# moire_v2_5.net
KiCad netlist of a schematic drawn in EAGLE
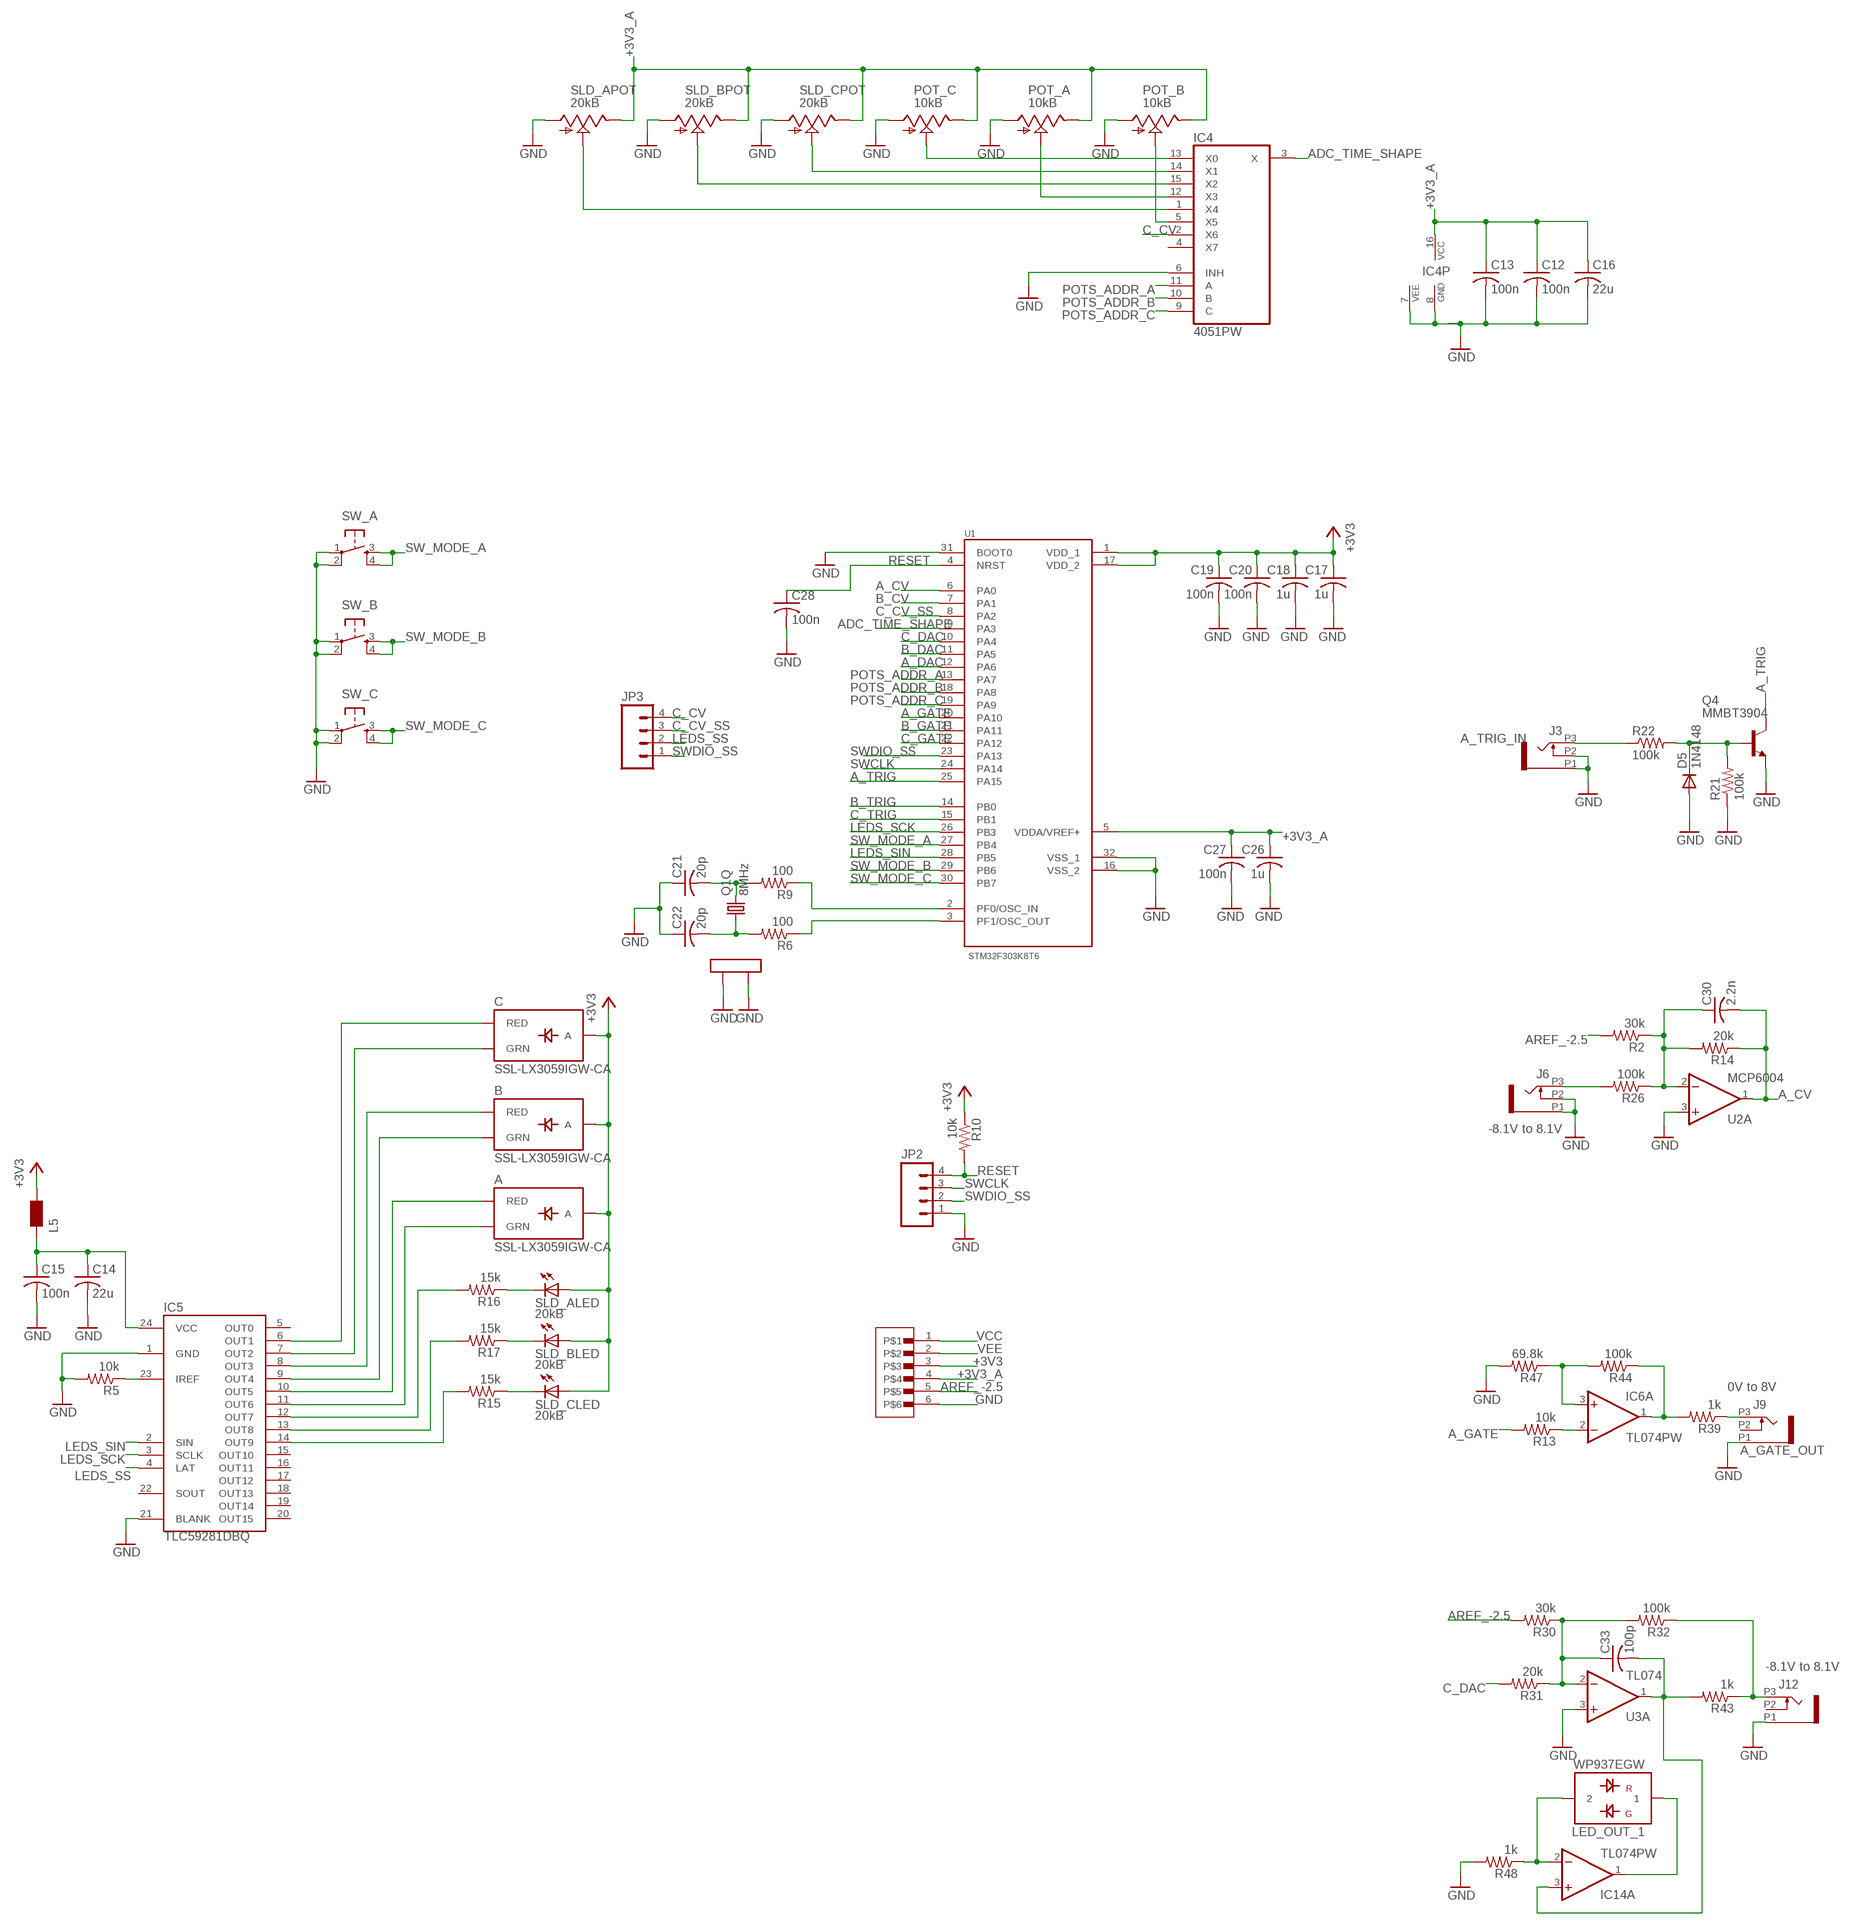
[diagram p0: schematic, sheet 1, part 1 of 2]
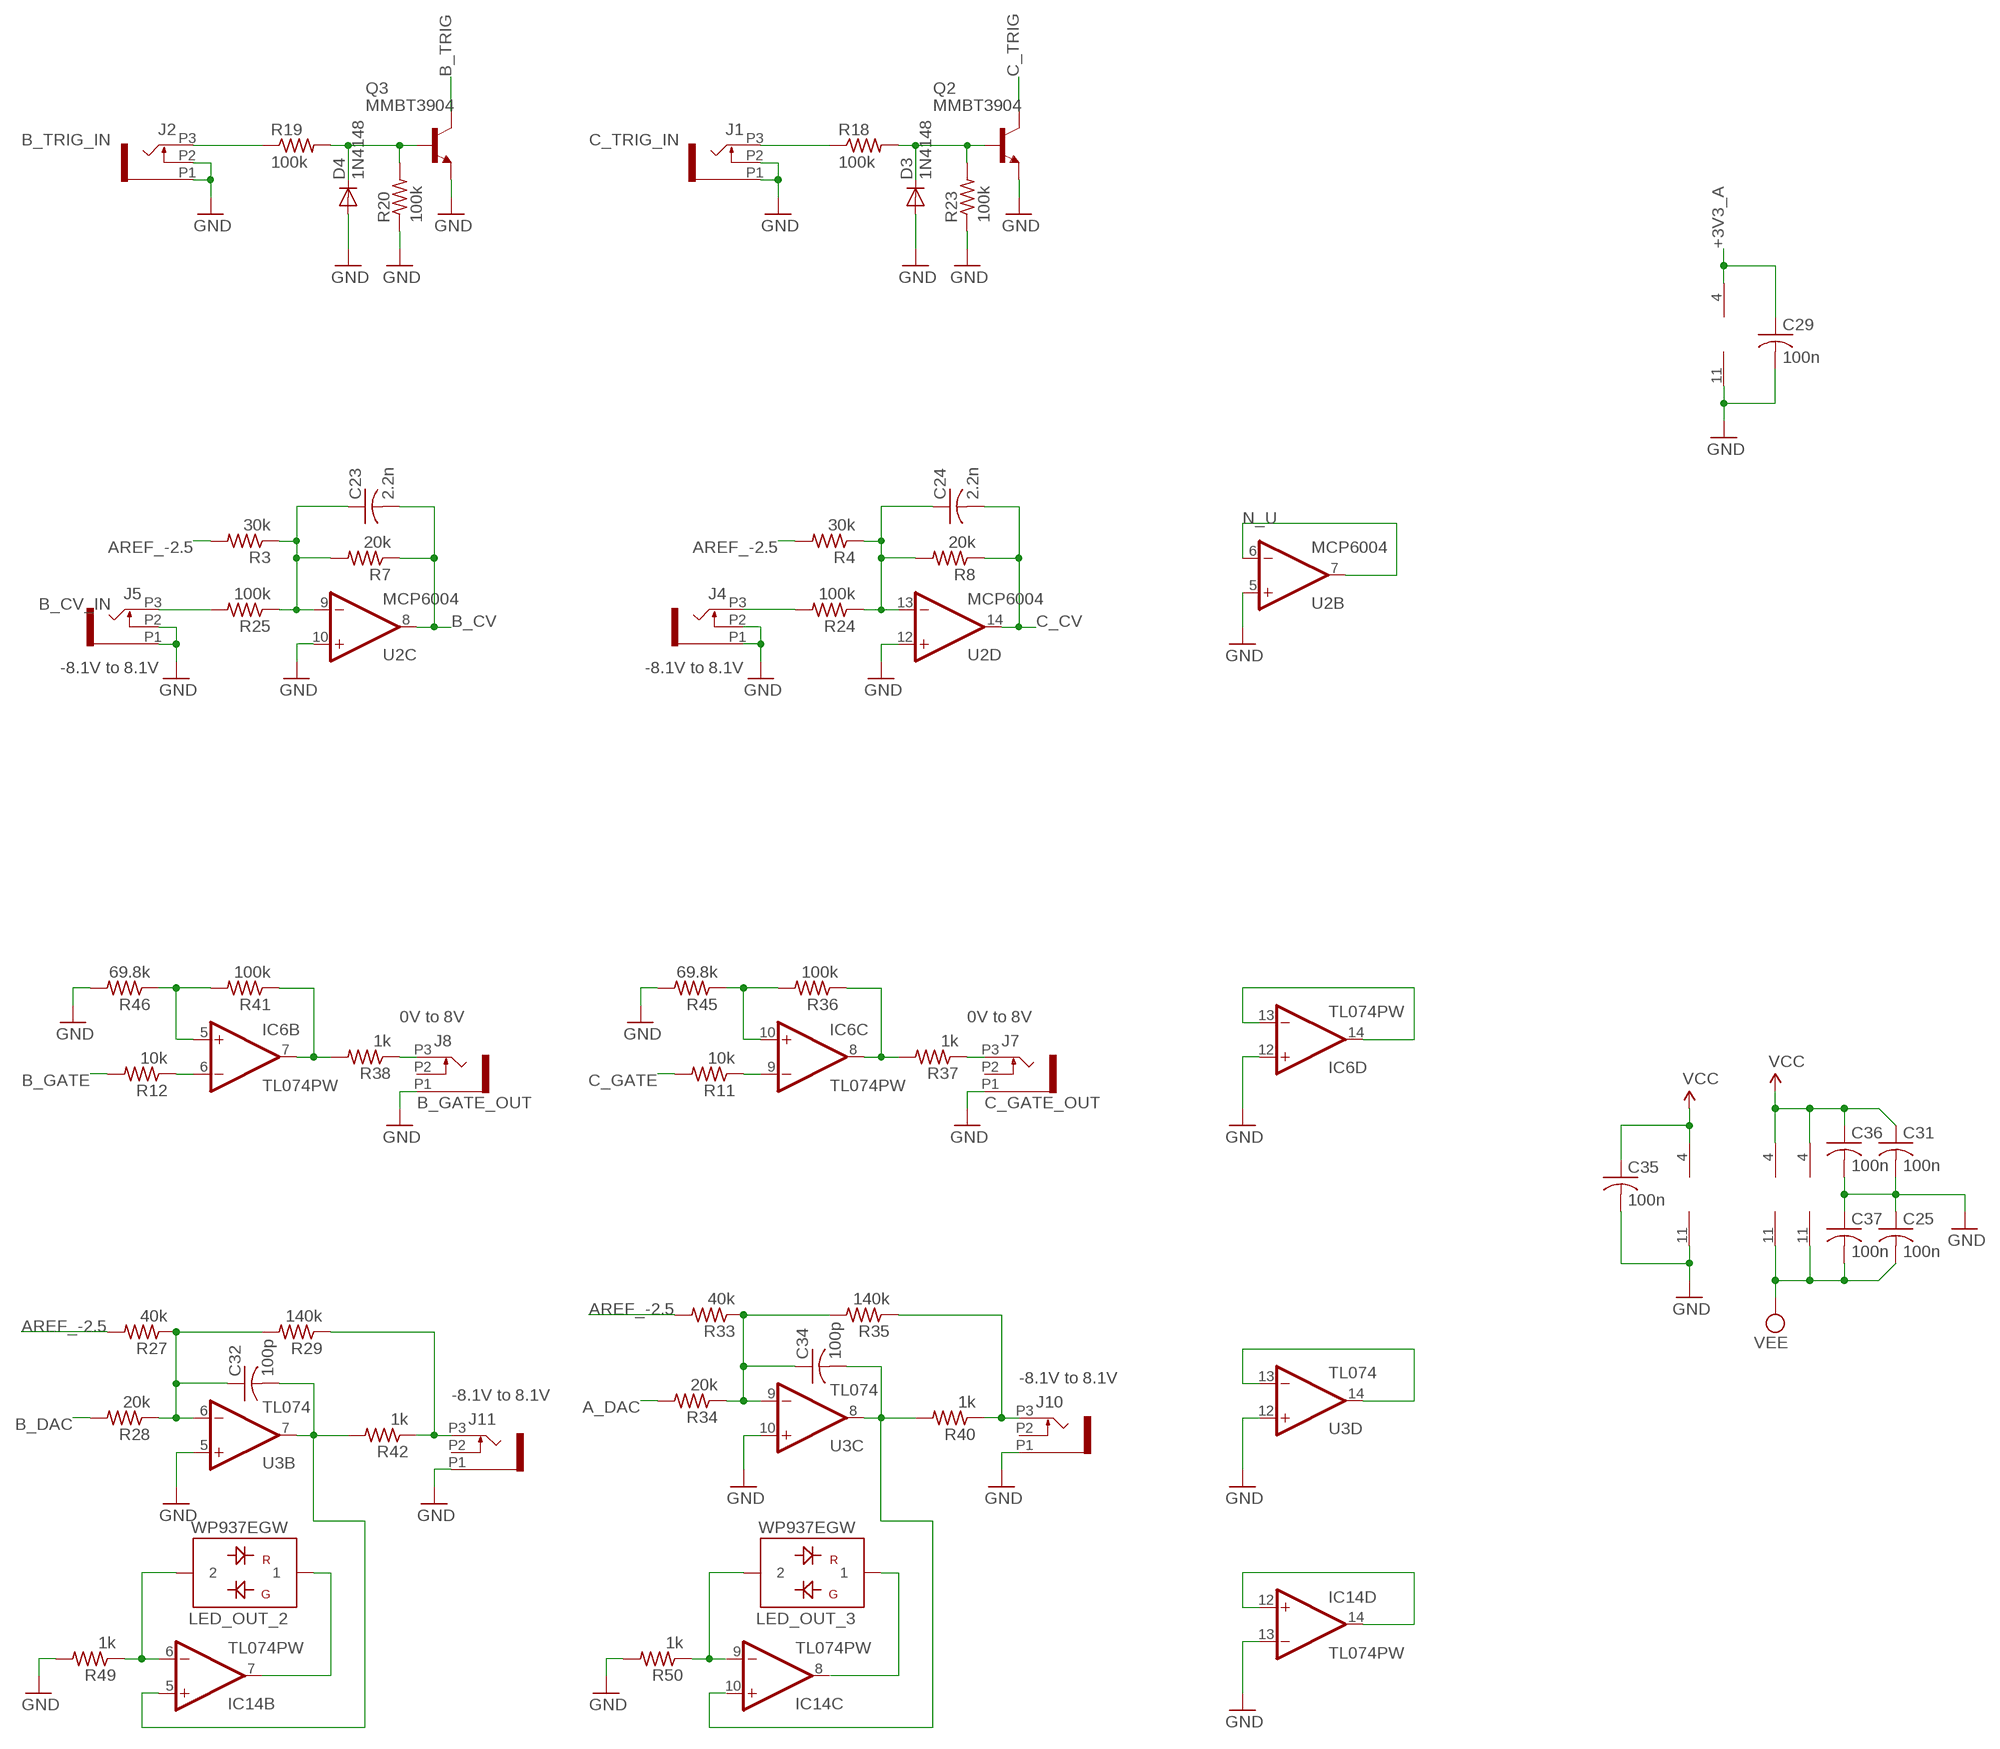
[diagram p1: schematic, sheet 1, part 2 of 2]
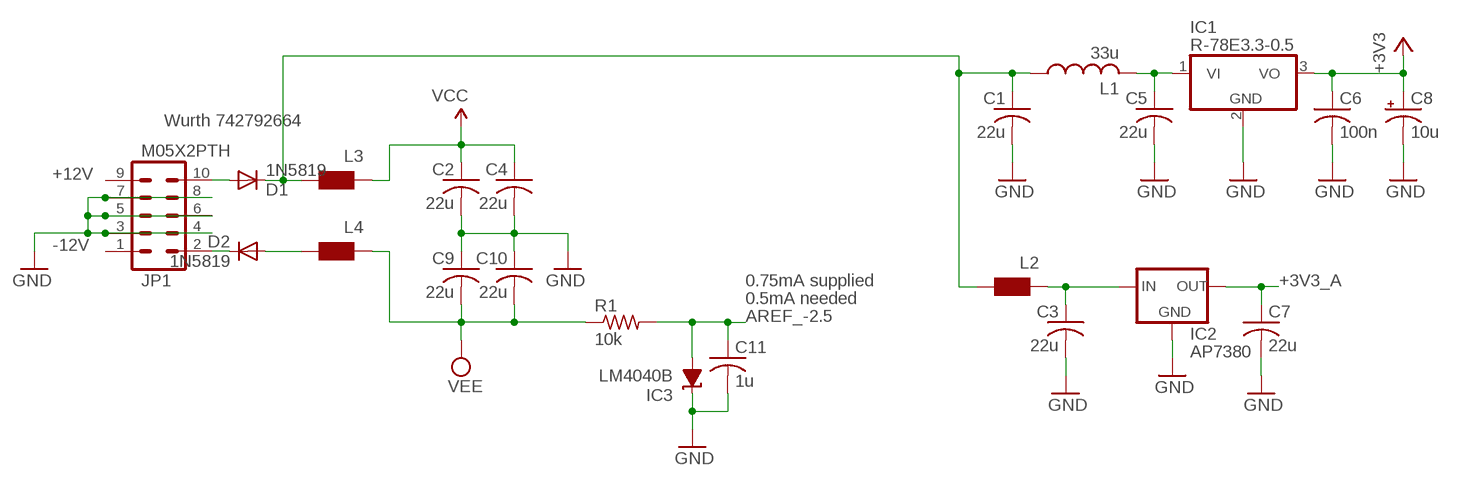
[diagram p2: schematic, sheet 2]

(export (version "E")
  (design (tool "Eeschema 10.0.6"))
  (components
    (comp (ref "C1")
      (value "22u")
      (footprint "eagle-import:RCL_C1206")
      (libsource (lib "eagle-import") (part "RCL_C-USC1206"))
    )
    (comp (ref "C2")
      (value "22u")
      (footprint "eagle-import:RCL_C1206")
      (libsource (lib "eagle-import") (part "RCL_C-USC1206"))
    )
    (comp (ref "C3")
      (value "22u")
      (footprint "eagle-import:RCL_C1206")
      (libsource (lib "eagle-import") (part "RCL_C-USC1206"))
    )
    (comp (ref "C4")
      (value "22u")
      (footprint "eagle-import:RCL_C1206")
      (libsource (lib "eagle-import") (part "RCL_C-USC1206"))
    )
    (comp (ref "C5")
      (value "22u")
      (footprint "eagle-import:RCL_C1206")
      (libsource (lib "eagle-import") (part "RCL_C-USC1206"))
    )
    (comp (ref "C6")
      (value "100n")
      (footprint "eagle-import:RCL_C0603")
      (libsource (lib "eagle-import") (part "RCL_C-USC0603"))
    )
    (comp (ref "C7")
      (value "22u")
      (footprint "eagle-import:RCL_C1206")
      (libsource (lib "eagle-import") (part "RCL_C-USC1206"))
    )
    (comp (ref "C8")
      (value "10u")
      (footprint "eagle-import:RCL_PANASONIC_A")
      (libsource (lib "eagle-import") (part "RCL_CPOL-USA"))
    )
    (comp (ref "C9")
      (value "22u")
      (footprint "eagle-import:RCL_C1206")
      (libsource (lib "eagle-import") (part "RCL_C-USC1206"))
    )
    (comp (ref "C10")
      (value "22u")
      (footprint "eagle-import:RCL_C1206")
      (libsource (lib "eagle-import") (part "RCL_C-USC1206"))
    )
    (comp (ref "C11")
      (value "1u")
      (footprint "eagle-import:RCL_C0603")
      (libsource (lib "eagle-import") (part "RCL_C-USC0603"))
    )
    (comp (ref "D1")
      (value "1N5819")
      (footprint "eagle-import:DIODE_SOD123")
      (libsource (lib "eagle-import") (part "DIODE_DIODE-SOD123"))
    )
    (comp (ref "D2")
      (value "1N5819")
      (footprint "eagle-import:DIODE_SOD123")
      (libsource (lib "eagle-import") (part "DIODE_DIODE-SOD123"))
    )
    (comp (ref "IC1")
      (value "R-78E3.3-0.5")
      (footprint "eagle-import:WE78")
      (libsource (lib "eagle-import") (part "WE173950378"))
    )
    (comp (ref "IC2")
      (value "AP7380")
      (footprint "eagle-import:SOT89")
      (libsource (lib "eagle-import") (part "AP7380"))
    )
    (comp (ref "IC3")
      (value "LM4040B")
      (footprint "eagle-import:DBZ_R-PDSO-G3")
      (libsource (lib "eagle-import") (part "LM4041DBZB12"))
    )
    (comp (ref "JP1")
      (value "M05X2PTH")
      (footprint "eagle-import:2X5-PTH")
      (libsource (lib "eagle-import") (part "M05X2PTH"))
    )
    (comp (ref "L1")
      (value "33u")
      (footprint "eagle-import:L2012C")
      (libsource (lib "eagle-import") (part "L-USL2012C"))
    )
    (comp (ref "L2")
      (value "WE-CBF_0603")
      (footprint "eagle-import:0603")
      (libsource (lib "eagle-import") (part "WE-CBF_0603"))
    )
    (comp (ref "L3")
      (value "WE-CBF_0603")
      (footprint "eagle-import:0603")
      (libsource (lib "eagle-import") (part "WE-CBF_0603"))
    )
    (comp (ref "L4")
      (value "WE-CBF_0603")
      (footprint "eagle-import:0603")
      (libsource (lib "eagle-import") (part "WE-CBF_0603"))
    )
    (comp (ref "R1")
      (value "10k")
      (footprint "eagle-import:RCL_R0603")
      (libsource (lib "eagle-import") (part "RCL_R-US_R0603"))
    )
    (comp (ref "A")
      (value "SSL-LX3059IGW-CA")
      (footprint "eagle-import:LED-BICOLOR-THROUGHHOLE-LUMEX")
      (libsource (lib "eagle-import") (part "LED-BICOLOR-THROUGHHOLE-CA"))
    )
    (comp (ref "B")
      (value "SSL-LX3059IGW-CA")
      (footprint "eagle-import:LED-BICOLOR-THROUGHHOLE-LUMEX")
      (libsource (lib "eagle-import") (part "LED-BICOLOR-THROUGHHOLE-CA"))
    )
    (comp (ref "C")
      (value "SSL-LX3059IGW-CA")
      (footprint "eagle-import:LED-BICOLOR-THROUGHHOLE-LUMEX")
      (libsource (lib "eagle-import") (part "LED-BICOLOR-THROUGHHOLE-CA"))
    )
    (comp (ref "C12")
      (value "100n")
      (footprint "eagle-import:RCL_C0603")
      (libsource (lib "eagle-import") (part "RCL_C-USC0603"))
    )
    (comp (ref "C13")
      (value "100n")
      (footprint "eagle-import:RCL_C0603")
      (libsource (lib "eagle-import") (part "RCL_C-USC0603"))
    )
    (comp (ref "C14")
      (value "22u")
      (footprint "eagle-import:RCL_C1206")
      (libsource (lib "eagle-import") (part "RCL_C-USC1206"))
    )
    (comp (ref "C15")
      (value "100n")
      (footprint "eagle-import:RCL_C0603")
      (libsource (lib "eagle-import") (part "RCL_C-USC0603"))
    )
    (comp (ref "C16")
      (value "22u")
      (footprint "eagle-import:RCL_C1206")
      (libsource (lib "eagle-import") (part "RCL_C-USC1206"))
    )
    (comp (ref "C17")
      (value "1u")
      (footprint "eagle-import:RCL_C0603")
      (libsource (lib "eagle-import") (part "RCL_C-USC0603"))
    )
    (comp (ref "C18")
      (value "1u")
      (footprint "eagle-import:RCL_C0603")
      (libsource (lib "eagle-import") (part "RCL_C-USC0603"))
    )
    (comp (ref "C19")
      (value "100n")
      (footprint "eagle-import:RCL_C0603")
      (libsource (lib "eagle-import") (part "RCL_C-USC0603"))
    )
    (comp (ref "C20")
      (value "100n")
      (footprint "eagle-import:RCL_C0603")
      (libsource (lib "eagle-import") (part "RCL_C-USC0603"))
    )
    (comp (ref "C21")
      (value "20p")
      (footprint "eagle-import:RCL_C0603")
      (libsource (lib "eagle-import") (part "RCL_C-USC0603"))
    )
    (comp (ref "C22")
      (value "20p")
      (footprint "eagle-import:RCL_C0603")
      (libsource (lib "eagle-import") (part "RCL_C-USC0603"))
    )
    (comp (ref "C23")
      (value "2.2n")
      (footprint "eagle-import:RCL_C0603")
      (libsource (lib "eagle-import") (part "RCL_C-USC0603"))
    )
    (comp (ref "C24")
      (value "2.2n")
      (footprint "eagle-import:RCL_C0603")
      (libsource (lib "eagle-import") (part "RCL_C-USC0603"))
    )
    (comp (ref "C25")
      (value "100n")
      (footprint "eagle-import:RCL_C0603")
      (libsource (lib "eagle-import") (part "RCL_C-USC0603"))
    )
    (comp (ref "C26")
      (value "1u")
      (footprint "eagle-import:RCL_C0603")
      (libsource (lib "eagle-import") (part "RCL_C-USC0603"))
    )
    (comp (ref "C27")
      (value "100n")
      (footprint "eagle-import:RCL_C0603")
      (libsource (lib "eagle-import") (part "RCL_C-USC0603"))
    )
    (comp (ref "C28")
      (value "100n")
      (footprint "eagle-import:RCL_C0603")
      (libsource (lib "eagle-import") (part "RCL_C-USC0603"))
    )
    (comp (ref "C29")
      (value "100n")
      (footprint "eagle-import:RCL_C0603")
      (libsource (lib "eagle-import") (part "RCL_C-USC0603"))
    )
    (comp (ref "C30")
      (value "2.2n")
      (footprint "eagle-import:RCL_C0603")
      (libsource (lib "eagle-import") (part "RCL_C-USC0603"))
    )
    (comp (ref "C31")
      (value "100n")
      (footprint "eagle-import:RCL_C0603")
      (libsource (lib "eagle-import") (part "RCL_C-USC0603"))
    )
    (comp (ref "C32")
      (value "100p")
      (footprint "eagle-import:RCL_C0603")
      (libsource (lib "eagle-import") (part "RCL_C-USC0603"))
    )
    (comp (ref "C33")
      (value "100p")
      (footprint "eagle-import:RCL_C0603")
      (libsource (lib "eagle-import") (part "RCL_C-USC0603"))
    )
    (comp (ref "C34")
      (value "100p")
      (footprint "eagle-import:RCL_C0603")
      (libsource (lib "eagle-import") (part "RCL_C-USC0603"))
    )
    (comp (ref "C35")
      (value "100n")
      (footprint "eagle-import:RCL_C0603")
      (libsource (lib "eagle-import") (part "RCL_C-USC0603"))
    )
    (comp (ref "C36")
      (value "100n")
      (footprint "eagle-import:RCL_C0603")
      (libsource (lib "eagle-import") (part "RCL_C-USC0603"))
    )
    (comp (ref "C37")
      (value "100n")
      (footprint "eagle-import:RCL_C0603")
      (libsource (lib "eagle-import") (part "RCL_C-USC0603"))
    )
    (comp (ref "D3")
      (value "1N4148")
      (footprint "eagle-import:DIODE_SOD323-R")
      (libsource (lib "eagle-import") (part "DIODE_DIODE-SOD323-R"))
    )
    (comp (ref "D4")
      (value "1N4148")
      (footprint "eagle-import:DIODE_SOD323-R")
      (libsource (lib "eagle-import") (part "DIODE_DIODE-SOD323-R"))
    )
    (comp (ref "D5")
      (value "1N4148")
      (footprint "eagle-import:DIODE_SOD323-R")
      (libsource (lib "eagle-import") (part "DIODE_DIODE-SOD323-R"))
    )
    (comp (ref "IC4")
      (value "4051PW")
      (footprint "eagle-import:TSSOP16_065")
      (libsource (lib "eagle-import") (part "4051PW"))
    )
    (comp (ref "IC5")
      (value "TLC59281DBQ")
      (footprint "eagle-import:TSSOP24_0635")
      (libsource (lib "eagle-import") (part "TLC59281DBQ"))
    )
    (comp (ref "IC6")
      (value "TL074PW")
      (footprint "eagle-import:TSSOP14_065")
      (libsource (lib "eagle-import") (part "og-linear_TL074PW"))
    )
    (comp (ref "IC14")
      (value "TL074PW")
      (footprint "eagle-import:TSSOP14_065")
      (libsource (lib "eagle-import") (part "TL074PW"))
    )
    (comp (ref "J1")
      (value "PJ301_THONKICONN6")
      (footprint "eagle-import:WQP_PJ_301M6")
      (libsource (lib "eagle-import") (part "PJ301_THONKICONN6"))
    )
    (comp (ref "J2")
      (value "PJ301_THONKICONN6")
      (footprint "eagle-import:WQP_PJ_301M6")
      (libsource (lib "eagle-import") (part "PJ301_THONKICONN6"))
    )
    (comp (ref "J3")
      (value "PJ301_THONKICONN6")
      (footprint "eagle-import:WQP_PJ_301M6")
      (libsource (lib "eagle-import") (part "PJ301_THONKICONN6"))
    )
    (comp (ref "J4")
      (value "PJ301_THONKICONN6")
      (footprint "eagle-import:WQP_PJ_301M6")
      (libsource (lib "eagle-import") (part "PJ301_THONKICONN6"))
    )
    (comp (ref "J5")
      (value "PJ301_THONKICONN6")
      (footprint "eagle-import:WQP_PJ_301M6")
      (libsource (lib "eagle-import") (part "PJ301_THONKICONN6"))
    )
    (comp (ref "J6")
      (value "PJ301_THONKICONN6")
      (footprint "eagle-import:WQP_PJ_301M6")
      (libsource (lib "eagle-import") (part "PJ301_THONKICONN6"))
    )
    (comp (ref "J7")
      (value "PJ301_THONKICONN6")
      (footprint "eagle-import:WQP_PJ_301M6")
      (libsource (lib "eagle-import") (part "PJ301_THONKICONN6"))
    )
    (comp (ref "J8")
      (value "PJ301_THONKICONN6")
      (footprint "eagle-import:WQP_PJ_301M6")
      (libsource (lib "eagle-import") (part "PJ301_THONKICONN6"))
    )
    (comp (ref "J9")
      (value "PJ301_THONKICONN6")
      (footprint "eagle-import:WQP_PJ_301M6")
      (libsource (lib "eagle-import") (part "PJ301_THONKICONN6"))
    )
    (comp (ref "J10")
      (value "PJ301_THONKICONN6")
      (footprint "eagle-import:WQP_PJ_301M6")
      (libsource (lib "eagle-import") (part "PJ301_THONKICONN6"))
    )
    (comp (ref "J11")
      (value "PJ301_THONKICONN6")
      (footprint "eagle-import:WQP_PJ_301M6")
      (libsource (lib "eagle-import") (part "PJ301_THONKICONN6"))
    )
    (comp (ref "J12")
      (value "PJ301_THONKICONN6")
      (footprint "eagle-import:WQP_PJ_301M6")
      (libsource (lib "eagle-import") (part "PJ301_THONKICONN6"))
    )
    (comp (ref "JP2")
      (value "M04PTH")
      (footprint "eagle-import:1X04")
      (libsource (lib "eagle-import") (part "M04PTH"))
    )
    (comp (ref "JP3")
      (value "M04PTH")
      (footprint "eagle-import:1X04")
      (libsource (lib "eagle-import") (part "M04PTH"))
    )
    (comp (ref "L5")
      (value "WE-CBF_0603")
      (footprint "eagle-import:0603")
      (libsource (lib "eagle-import") (part "WE-CBF_0603"))
    )
    (comp (ref "LED_OUT_1")
      (value "WP937EGW")
      (footprint "eagle-import:LED3MM")
      (libsource (lib "eagle-import") (part "LED-BICOLOR-SHARED-THROUGHHOLE"))
    )
    (comp (ref "LED_OUT_2")
      (value "WP937EGW")
      (footprint "eagle-import:LED3MM")
      (libsource (lib "eagle-import") (part "LED-BICOLOR-SHARED-THROUGHHOLE"))
    )
    (comp (ref "LED_OUT_3")
      (value "WP937EGW")
      (footprint "eagle-import:LED3MM")
      (libsource (lib "eagle-import") (part "LED-BICOLOR-SHARED-THROUGHHOLE"))
    )
    (comp (ref "POT_A")
      (value "10kB")
      (footprint "eagle-import:ALPS_POT_VERTICAL")
      (libsource (lib "eagle-import") (part "POT_USVERTICAL"))
    )
    (comp (ref "POT_B")
      (value "10kB")
      (footprint "eagle-import:ALPS_POT_VERTICAL")
      (libsource (lib "eagle-import") (part "POT_USVERTICAL"))
    )
    (comp (ref "POT_C")
      (value "10kB")
      (footprint "eagle-import:ALPS_POT_VERTICAL")
      (libsource (lib "eagle-import") (part "POT_USVERTICAL"))
    )
    (comp (ref "Q1")
      (value "8MHz")
      (footprint "eagle-import:CTS406")
      (libsource (lib "eagle-import") (part "CRYSTAL"))
    )
    (comp (ref "Q2")
      (value "MMBT3904")
      (footprint "eagle-import:SOT23-BEC")
      (libsource (lib "eagle-import") (part "-NPN-SOT23-BECMMBT3904LT1"))
    )
    (comp (ref "Q3")
      (value "MMBT3904")
      (footprint "eagle-import:SOT23-BEC")
      (libsource (lib "eagle-import") (part "-NPN-SOT23-BECMMBT3904LT1"))
    )
    (comp (ref "Q4")
      (value "MMBT3904")
      (footprint "eagle-import:SOT23-BEC")
      (libsource (lib "eagle-import") (part "-NPN-SOT23-BECMMBT3904LT1"))
    )
    (comp (ref "R2")
      (value "30k")
      (footprint "eagle-import:RCL_R0603")
      (libsource (lib "eagle-import") (part "RCL_R-US_R0603"))
    )
    (comp (ref "R3")
      (value "30k")
      (footprint "eagle-import:RCL_R0603")
      (libsource (lib "eagle-import") (part "RCL_R-US_R0603"))
    )
    (comp (ref "R4")
      (value "30k")
      (footprint "eagle-import:RCL_R0603")
      (libsource (lib "eagle-import") (part "RCL_R-US_R0603"))
    )
    (comp (ref "R5")
      (value "10k")
      (footprint "eagle-import:RCL_R0603")
      (libsource (lib "eagle-import") (part "RCL_R-US_R0603"))
    )
    (comp (ref "R6")
      (value "100")
      (footprint "eagle-import:RCL_R0603")
      (libsource (lib "eagle-import") (part "RCL_R-US_R0603"))
    )
    (comp (ref "R7")
      (value "20k")
      (footprint "eagle-import:RCL_R0603")
      (libsource (lib "eagle-import") (part "RCL_R-US_R0603"))
    )
    (comp (ref "R8")
      (value "20k")
      (footprint "eagle-import:RCL_R0603")
      (libsource (lib "eagle-import") (part "RCL_R-US_R0603"))
    )
    (comp (ref "R9")
      (value "100")
      (footprint "eagle-import:RCL_R0603")
      (libsource (lib "eagle-import") (part "RCL_R-US_R0603"))
    )
    (comp (ref "R10")
      (value "10k")
      (footprint "eagle-import:RCL_R0603")
      (libsource (lib "eagle-import") (part "RCL_R-US_R0603"))
    )
    (comp (ref "R11")
      (value "10k")
      (footprint "eagle-import:RCL_R0603")
      (libsource (lib "eagle-import") (part "RCL_R-US_R0603"))
    )
    (comp (ref "R12")
      (value "10k")
      (footprint "eagle-import:RCL_R0603")
      (libsource (lib "eagle-import") (part "RCL_R-US_R0603"))
    )
    (comp (ref "R13")
      (value "10k")
      (footprint "eagle-import:RCL_R0603")
      (libsource (lib "eagle-import") (part "RCL_R-US_R0603"))
    )
    (comp (ref "R14")
      (value "20k")
      (footprint "eagle-import:RCL_R0603")
      (libsource (lib "eagle-import") (part "RCL_R-US_R0603"))
    )
    (comp (ref "R15")
      (value "15k")
      (footprint "eagle-import:RCL_R0603")
      (libsource (lib "eagle-import") (part "RCL_R-US_R0603"))
    )
    (comp (ref "R16")
      (value "15k")
      (footprint "eagle-import:RCL_R0603")
      (libsource (lib "eagle-import") (part "RCL_R-US_R0603"))
    )
    (comp (ref "R17")
      (value "15k")
      (footprint "eagle-import:RCL_R0603")
      (libsource (lib "eagle-import") (part "RCL_R-US_R0603"))
    )
    (comp (ref "R18")
      (value "100k")
      (footprint "eagle-import:RCL_R0603")
      (libsource (lib "eagle-import") (part "RCL_R-US_R0603"))
    )
    (comp (ref "R19")
      (value "100k")
      (footprint "eagle-import:RCL_R0603")
      (libsource (lib "eagle-import") (part "RCL_R-US_R0603"))
    )
    (comp (ref "R20")
      (value "100k")
      (footprint "eagle-import:RCL_R0603")
      (libsource (lib "eagle-import") (part "RCL_R-US_R0603"))
    )
    (comp (ref "R21")
      (value "100k")
      (footprint "eagle-import:RCL_R0603")
      (libsource (lib "eagle-import") (part "RCL_R-US_R0603"))
    )
    (comp (ref "R22")
      (value "100k")
      (footprint "eagle-import:RCL_R0603")
      (libsource (lib "eagle-import") (part "RCL_R-US_R0603"))
    )
    (comp (ref "R23")
      (value "100k")
      (footprint "eagle-import:RCL_R0603")
      (libsource (lib "eagle-import") (part "RCL_R-US_R0603"))
    )
    (comp (ref "R24")
      (value "100k")
      (footprint "eagle-import:RCL_R0603")
      (libsource (lib "eagle-import") (part "RCL_R-US_R0603"))
    )
    (comp (ref "R25")
      (value "100k")
      (footprint "eagle-import:RCL_R0603")
      (libsource (lib "eagle-import") (part "RCL_R-US_R0603"))
    )
    (comp (ref "R26")
      (value "100k")
      (footprint "eagle-import:RCL_R0603")
      (libsource (lib "eagle-import") (part "RCL_R-US_R0603"))
    )
    (comp (ref "R27")
      (value "40k")
      (footprint "eagle-import:RCL_R0603")
      (libsource (lib "eagle-import") (part "RCL_R-US_R0603"))
    )
    (comp (ref "R28")
      (value "20k")
      (footprint "eagle-import:RCL_R0603")
      (libsource (lib "eagle-import") (part "RCL_R-US_R0603"))
    )
    (comp (ref "R29")
      (value "140k")
      (footprint "eagle-import:RCL_R0603")
      (libsource (lib "eagle-import") (part "RCL_R-US_R0603"))
    )
    (comp (ref "R30")
      (value "30k")
      (footprint "eagle-import:RCL_R0603")
      (libsource (lib "eagle-import") (part "RCL_R-US_R0603"))
    )
    (comp (ref "R31")
      (value "20k")
      (footprint "eagle-import:RCL_R0603")
      (libsource (lib "eagle-import") (part "RCL_R-US_R0603"))
    )
    (comp (ref "R32")
      (value "100k")
      (footprint "eagle-import:RCL_R0603")
      (libsource (lib "eagle-import") (part "RCL_R-US_R0603"))
    )
    (comp (ref "R33")
      (value "40k")
      (footprint "eagle-import:RCL_R0603")
      (libsource (lib "eagle-import") (part "RCL_R-US_R0603"))
    )
    (comp (ref "R34")
      (value "20k")
      (footprint "eagle-import:RCL_R0603")
      (libsource (lib "eagle-import") (part "RCL_R-US_R0603"))
    )
    (comp (ref "R35")
      (value "140k")
      (footprint "eagle-import:RCL_R0603")
      (libsource (lib "eagle-import") (part "RCL_R-US_R0603"))
    )
    (comp (ref "R36")
      (value "100k")
      (footprint "eagle-import:RCL_R0603")
      (libsource (lib "eagle-import") (part "RCL_R-US_R0603"))
    )
    (comp (ref "R37")
      (value "1k")
      (footprint "eagle-import:RCL_R0603")
      (libsource (lib "eagle-import") (part "RCL_R-US_R0603"))
    )
    (comp (ref "R38")
      (value "1k")
      (footprint "eagle-import:RCL_R0603")
      (libsource (lib "eagle-import") (part "RCL_R-US_R0603"))
    )
    (comp (ref "R39")
      (value "1k")
      (footprint "eagle-import:RCL_R0603")
      (libsource (lib "eagle-import") (part "RCL_R-US_R0603"))
    )
    (comp (ref "R40")
      (value "1k")
      (footprint "eagle-import:RCL_R0603")
      (libsource (lib "eagle-import") (part "RCL_R-US_R0603"))
    )
    (comp (ref "R41")
      (value "100k")
      (footprint "eagle-import:RCL_R0603")
      (libsource (lib "eagle-import") (part "RCL_R-US_R0603"))
    )
    (comp (ref "R42")
      (value "1k")
      (footprint "eagle-import:RCL_R0603")
      (libsource (lib "eagle-import") (part "RCL_R-US_R0603"))
    )
    (comp (ref "R43")
      (value "1k")
      (footprint "eagle-import:RCL_R0603")
      (libsource (lib "eagle-import") (part "RCL_R-US_R0603"))
    )
    (comp (ref "R44")
      (value "100k")
      (footprint "eagle-import:RCL_R0603")
      (libsource (lib "eagle-import") (part "RCL_R-US_R0603"))
    )
    (comp (ref "R45")
      (value "69.8k")
      (footprint "eagle-import:RCL_R0603")
      (libsource (lib "eagle-import") (part "RCL_R-US_R0603"))
    )
    (comp (ref "R46")
      (value "69.8k")
      (footprint "eagle-import:RCL_R0603")
      (libsource (lib "eagle-import") (part "RCL_R-US_R0603"))
    )
    (comp (ref "R47")
      (value "69.8k")
      (footprint "eagle-import:RCL_R0603")
      (libsource (lib "eagle-import") (part "RCL_R-US_R0603"))
    )
    (comp (ref "R48")
      (value "1k")
      (footprint "eagle-import:RCL_R0603")
      (libsource (lib "eagle-import") (part "RCL_R-US_R0603"))
    )
    (comp (ref "R49")
      (value "1k")
      (footprint "eagle-import:RCL_R0603")
      (libsource (lib "eagle-import") (part "RCL_R-US_R0603"))
    )
    (comp (ref "R50")
      (value "1k")
      (footprint "eagle-import:RCL_R0603")
      (libsource (lib "eagle-import") (part "RCL_R-US_R0603"))
    )
    (comp (ref "SLD_A")
      (value "20kB")
      (footprint "eagle-import:BOURNS_SLIDER")
      (libsource (lib "eagle-import") (part "BOURNS_SLIDER"))
    )
    (comp (ref "SLD_B")
      (value "20kB")
      (footprint "eagle-import:BOURNS_SLIDER")
      (libsource (lib "eagle-import") (part "BOURNS_SLIDER"))
    )
    (comp (ref "SLD_C")
      (value "20kB")
      (footprint "eagle-import:BOURNS_SLIDER")
      (libsource (lib "eagle-import") (part "BOURNS_SLIDER"))
    )
    (comp (ref "SW_A")
      (value "TAC_SWITCHPTH")
      (footprint "eagle-import:TACTILE-PTH")
      (libsource (lib "eagle-import") (part "TAC_SWITCHPTH"))
    )
    (comp (ref "SW_B")
      (value "TAC_SWITCHPTH")
      (footprint "eagle-import:TACTILE-PTH")
      (libsource (lib "eagle-import") (part "TAC_SWITCHPTH"))
    )
    (comp (ref "SW_C")
      (value "TAC_SWITCHPTH")
      (footprint "eagle-import:TACTILE-PTH")
      (libsource (lib "eagle-import") (part "TAC_SWITCHPTH"))
    )
    (comp (ref "U$1")
      (value "1X6-SMD-TESTPAD")
      (footprint "eagle-import:6X1-SMD-TESTPAD")
      (libsource (lib "eagle-import") (part "1X6-SMD-TESTPAD"))
    )
    (comp (ref "U1")
      (value "STM32F303K8T6")
      (footprint "eagle-import:QFP80P900X900X160-32N")
      (fields (field (name "MF") "STMicroelectronics"))
      (libsource (lib "eagle-import") (part "STM32F303K8T6"))
    )
    (comp (ref "U2")
      (value "MCP6004")
      (footprint "eagle-import:SO14")
      (libsource (lib "eagle-import") (part "MCP6004_SMD"))
    )
    (comp (ref "U3")
      (value "TL074")
      (footprint "eagle-import:SO14")
      (libsource (lib "eagle-import") (part "TL074_SMD"))
    )
  )
  (nets
    (net (code "1") (name "+3V3") (class "Default")
      (node (ref "A") (pin "A") (pinfunction "A_A") (pintype "bidirectional"))
      (node (ref "B") (pin "A") (pinfunction "A_A") (pintype "bidirectional"))
      (node (ref "C") (pin "A") (pinfunction "A_A") (pintype "bidirectional"))
      (node (ref "C17") (pin "1") (pinfunction "1_1") (pintype "passive"))
      (node (ref "C18") (pin "1") (pinfunction "1_1") (pintype "passive"))
      (node (ref "C19") (pin "1") (pinfunction "1_1") (pintype "passive"))
      (node (ref "C20") (pin "1") (pinfunction "1_1") (pintype "passive"))
      (node (ref "C6") (pin "1") (pinfunction "1_1") (pintype "passive"))
      (node (ref "C8") (pin "+") (pinfunction "+_+") (pintype "passive"))
      (node (ref "IC1") (pin "3") (pinfunction "VO_3") (pintype "passive"))
      (node (ref "L5") (pin "2") (pinfunction "2_2") (pintype "passive"))
      (node (ref "R10") (pin "1") (pinfunction "1_1") (pintype "passive"))
      (node (ref "SLD_A") (pin "B") (pinfunction "A_B") (pintype "passive"))
      (node (ref "SLD_B") (pin "B") (pinfunction "A_B") (pintype "passive"))
      (node (ref "SLD_C") (pin "B") (pinfunction "A_B") (pintype "passive"))
      (node (ref "U$1") (pin "3") (pinfunction "P$3_3") (pintype "bidirectional"))
      (node (ref "U1") (pin "1") (pinfunction "VDD_1_1") (pintype "power_in"))
      (node (ref "U1") (pin "17") (pinfunction "VDD_2_17") (pintype "power_in"))
    )
    (net (code "2") (name "+3V3_A") (class "Default")
      (node (ref "C12") (pin "1") (pinfunction "1_1") (pintype "passive"))
      (node (ref "C13") (pin "1") (pinfunction "1_1") (pintype "passive"))
      (node (ref "C16") (pin "1") (pinfunction "1_1") (pintype "passive"))
      (node (ref "C26") (pin "1") (pinfunction "1_1") (pintype "passive"))
      (node (ref "C27") (pin "1") (pinfunction "1_1") (pintype "passive"))
      (node (ref "C29") (pin "1") (pinfunction "1_1") (pintype "passive"))
      (node (ref "C7") (pin "1") (pinfunction "1_1") (pintype "passive"))
      (node (ref "IC2") (pin "3") (pinfunction "OUT_3") (pintype "passive"))
      (node (ref "IC4") (pin "16") (pinfunction "VCC_16") (pintype "power_in"))
      (node (ref "POT_A") (pin "P$1") (pinfunction "E_P$1") (pintype "passive"))
      (node (ref "POT_B") (pin "P$1") (pinfunction "E_P$1") (pintype "passive"))
      (node (ref "POT_C") (pin "P$1") (pinfunction "E_P$1") (pintype "passive"))
      (node (ref "SLD_A") (pin "3") (pinfunction "E_3") (pintype "passive"))
      (node (ref "SLD_B") (pin "3") (pinfunction "E_3") (pintype "passive"))
      (node (ref "SLD_C") (pin "3") (pinfunction "E_3") (pintype "passive"))
      (node (ref "U$1") (pin "4") (pinfunction "P$4_4") (pintype "bidirectional"))
      (node (ref "U1") (pin "5") (pinfunction "VDDA/VREF+_5") (pintype "power_in"))
      (node (ref "U2") (pin "4") (pinfunction "V+_4") (pintype "power_in"))
    )
    (net (code "3") (name "+12V") (class "Default")
      (node (ref "D1") (pin "A") (pinfunction "A_A") (pintype "passive"))
      (node (ref "JP1") (pin "10") (pinfunction "10_10") (pintype "passive"))
      (node (ref "JP1") (pin "9") (pinfunction "9_9") (pintype "passive"))
    )
    (net (code "4") (name "-12V") (class "Default")
      (node (ref "D2") (pin "C") (pinfunction "C_C") (pintype "passive"))
      (node (ref "JP1") (pin "1") (pinfunction "1_1") (pintype "passive"))
      (node (ref "JP1") (pin "2") (pinfunction "2_2") (pintype "passive"))
    )
    (net (code "5") (name "ADC_TIME_SHAPE") (class "Default")
      (node (ref "IC4") (pin "3") (pinfunction "X_3") (pintype "bidirectional"))
      (node (ref "U1") (pin "9") (pinfunction "PA3_9") (pintype "bidirectional"))
    )
    (net (code "6") (name "AREF_-2.5") (class "Default")
      (node (ref "C11") (pin "1") (pinfunction "1_1") (pintype "passive"))
      (node (ref "IC3") (pin "2") (pinfunction "A_2") (pintype "passive"))
      (node (ref "R1") (pin "2") (pinfunction "2_2") (pintype "passive"))
      (node (ref "R2") (pin "2") (pinfunction "2_2") (pintype "passive"))
      (node (ref "R27") (pin "2") (pinfunction "2_2") (pintype "passive"))
      (node (ref "R3") (pin "2") (pinfunction "2_2") (pintype "passive"))
      (node (ref "R30") (pin "2") (pinfunction "2_2") (pintype "passive"))
      (node (ref "R33") (pin "2") (pinfunction "2_2") (pintype "passive"))
      (node (ref "R4") (pin "2") (pinfunction "2_2") (pintype "passive"))
      (node (ref "U$1") (pin "5") (pinfunction "P$5_5") (pintype "bidirectional"))
    )
    (net (code "7") (name "A_CV") (class "Default")
      (node (ref "C30") (pin "2") (pinfunction "2_2") (pintype "passive"))
      (node (ref "R14") (pin "1") (pinfunction "1_1") (pintype "passive"))
      (node (ref "U1") (pin "6") (pinfunction "PA0_6") (pintype "bidirectional"))
      (node (ref "U2") (pin "1") (pinfunction "OUT_1") (pintype "output"))
    )
    (net (code "8") (name "A_DAC") (class "Default")
      (node (ref "R34") (pin "2") (pinfunction "2_2") (pintype "passive"))
      (node (ref "U1") (pin "12") (pinfunction "PA6_12") (pintype "bidirectional"))
    )
    (net (code "9") (name "A_GATE") (class "Default")
      (node (ref "R13") (pin "2") (pinfunction "2_2") (pintype "passive"))
      (node (ref "U1") (pin "20") (pinfunction "PA10_20") (pintype "bidirectional"))
    )
    (net (code "10") (name "A_GATE_OUT") (class "Default")
      (node (ref "J9") (pin "P3") (pinfunction "3_P3") (pintype "passive"))
      (node (ref "R39") (pin "1") (pinfunction "1_1") (pintype "passive"))
    )
    (net (code "11") (name "A_TRIG") (class "Default")
      (node (ref "Q4") (pin "C") (pinfunction "C_C") (pintype "passive"))
      (node (ref "U1") (pin "25") (pinfunction "PA15_25") (pintype "bidirectional"))
    )
    (net (code "12") (name "A_TRIG_IN") (class "Default")
      (node (ref "J3") (pin "P3") (pinfunction "3_P3") (pintype "passive"))
      (node (ref "R22") (pin "1") (pinfunction "1_1") (pintype "passive"))
    )
    (net (code "13") (name "B_CV") (class "Default")
      (node (ref "C23") (pin "2") (pinfunction "2_2") (pintype "passive"))
      (node (ref "R7") (pin "1") (pinfunction "1_1") (pintype "passive"))
      (node (ref "U1") (pin "7") (pinfunction "PA1_7") (pintype "bidirectional"))
      (node (ref "U2") (pin "8") (pinfunction "OUT_8") (pintype "output"))
    )
    (net (code "14") (name "B_CV_IN") (class "Default")
      (node (ref "J5") (pin "P3") (pinfunction "3_P3") (pintype "passive"))
      (node (ref "R25") (pin "2") (pinfunction "2_2") (pintype "passive"))
    )
    (net (code "15") (name "B_DAC") (class "Default")
      (node (ref "R28") (pin "2") (pinfunction "2_2") (pintype "passive"))
      (node (ref "U1") (pin "11") (pinfunction "PA5_11") (pintype "bidirectional"))
    )
    (net (code "16") (name "B_GATE") (class "Default")
      (node (ref "R12") (pin "2") (pinfunction "2_2") (pintype "passive"))
      (node (ref "U1") (pin "21") (pinfunction "PA11_21") (pintype "bidirectional"))
    )
    (net (code "17") (name "B_GATE_OUT") (class "Default")
      (node (ref "J8") (pin "P3") (pinfunction "3_P3") (pintype "passive"))
      (node (ref "R38") (pin "1") (pinfunction "1_1") (pintype "passive"))
    )
    (net (code "18") (name "B_TRIG") (class "Default")
      (node (ref "Q3") (pin "C") (pinfunction "C_C") (pintype "passive"))
      (node (ref "U1") (pin "14") (pinfunction "PB0_14") (pintype "bidirectional"))
    )
    (net (code "19") (name "B_TRIG_IN") (class "Default")
      (node (ref "J2") (pin "P3") (pinfunction "3_P3") (pintype "passive"))
      (node (ref "R19") (pin "1") (pinfunction "1_1") (pintype "passive"))
    )
    (net (code "20") (name "C_CV") (class "Default")
      (node (ref "C24") (pin "2") (pinfunction "2_2") (pintype "passive"))
      (node (ref "IC4") (pin "2") (pinfunction "X6_2") (pintype "bidirectional"))
      (node (ref "JP3") (pin "4") (pinfunction "4_4") (pintype "passive"))
      (node (ref "R8") (pin "1") (pinfunction "1_1") (pintype "passive"))
      (node (ref "U2") (pin "14") (pinfunction "OUT_14") (pintype "output"))
    )
    (net (code "21") (name "C_CV_SS") (class "Default")
      (node (ref "JP3") (pin "3") (pinfunction "3_3") (pintype "passive"))
      (node (ref "U1") (pin "8") (pinfunction "PA2_8") (pintype "bidirectional"))
    )
    (net (code "22") (name "C_DAC") (class "Default")
      (node (ref "R31") (pin "2") (pinfunction "2_2") (pintype "passive"))
      (node (ref "U1") (pin "10") (pinfunction "PA4_10") (pintype "bidirectional"))
    )
    (net (code "23") (name "C_GATE") (class "Default")
      (node (ref "R11") (pin "2") (pinfunction "2_2") (pintype "passive"))
      (node (ref "U1") (pin "22") (pinfunction "PA12_22") (pintype "bidirectional"))
    )
    (net (code "24") (name "C_GATE_OUT") (class "Default")
      (node (ref "J7") (pin "P3") (pinfunction "3_P3") (pintype "passive"))
      (node (ref "R37") (pin "1") (pinfunction "1_1") (pintype "passive"))
    )
    (net (code "25") (name "C_TRIG") (class "Default")
      (node (ref "Q2") (pin "C") (pinfunction "C_C") (pintype "passive"))
      (node (ref "U1") (pin "15") (pinfunction "PB1_15") (pintype "bidirectional"))
    )
    (net (code "26") (name "C_TRIG_IN") (class "Default")
      (node (ref "J1") (pin "P3") (pinfunction "3_P3") (pintype "passive"))
      (node (ref "R18") (pin "1") (pinfunction "1_1") (pintype "passive"))
    )
    (net (code "27") (name "GND") (class "Default")
      (node (ref "C1") (pin "2") (pinfunction "2_2") (pintype "passive"))
      (node (ref "C10") (pin "1") (pinfunction "1_1") (pintype "passive"))
      (node (ref "C11") (pin "2") (pinfunction "2_2") (pintype "passive"))
      (node (ref "C12") (pin "2") (pinfunction "2_2") (pintype "passive"))
      (node (ref "C13") (pin "2") (pinfunction "2_2") (pintype "passive"))
      (node (ref "C14") (pin "2") (pinfunction "2_2") (pintype "passive"))
      (node (ref "C15") (pin "2") (pinfunction "2_2") (pintype "passive"))
      (node (ref "C16") (pin "2") (pinfunction "2_2") (pintype "passive"))
      (node (ref "C17") (pin "2") (pinfunction "2_2") (pintype "passive"))
      (node (ref "C18") (pin "2") (pinfunction "2_2") (pintype "passive"))
      (node (ref "C19") (pin "2") (pinfunction "2_2") (pintype "passive"))
      (node (ref "C2") (pin "2") (pinfunction "2_2") (pintype "passive"))
      (node (ref "C20") (pin "2") (pinfunction "2_2") (pintype "passive"))
      (node (ref "C21") (pin "1") (pinfunction "1_1") (pintype "passive"))
      (node (ref "C22") (pin "1") (pinfunction "1_1") (pintype "passive"))
      (node (ref "C25") (pin "1") (pinfunction "1_1") (pintype "passive"))
      (node (ref "C26") (pin "2") (pinfunction "2_2") (pintype "passive"))
      (node (ref "C27") (pin "2") (pinfunction "2_2") (pintype "passive"))
      (node (ref "C28") (pin "2") (pinfunction "2_2") (pintype "passive"))
      (node (ref "C29") (pin "2") (pinfunction "2_2") (pintype "passive"))
      (node (ref "C3") (pin "2") (pinfunction "2_2") (pintype "passive"))
      (node (ref "C31") (pin "2") (pinfunction "2_2") (pintype "passive"))
      (node (ref "C35") (pin "2") (pinfunction "2_2") (pintype "passive"))
      (node (ref "C36") (pin "2") (pinfunction "2_2") (pintype "passive"))
      (node (ref "C37") (pin "1") (pinfunction "1_1") (pintype "passive"))
      (node (ref "C4") (pin "2") (pinfunction "2_2") (pintype "passive"))
      (node (ref "C5") (pin "2") (pinfunction "2_2") (pintype "passive"))
      (node (ref "C6") (pin "2") (pinfunction "2_2") (pintype "passive"))
      (node (ref "C7") (pin "2") (pinfunction "2_2") (pintype "passive"))
      (node (ref "C8") (pin "-") (pinfunction "-_-") (pintype "passive"))
      (node (ref "C9") (pin "1") (pinfunction "1_1") (pintype "passive"))
      (node (ref "D3") (pin "A") (pinfunction "A_A") (pintype "passive"))
      (node (ref "D4") (pin "A") (pinfunction "A_A") (pintype "passive"))
      (node (ref "D5") (pin "A") (pinfunction "A_A") (pintype "passive"))
      (node (ref "IC1") (pin "2") (pinfunction "GND_2") (pintype "passive"))
      (node (ref "IC14") (pin "13") (pinfunction "-IN_13") (pintype "input"))
      (node (ref "IC2") (pin "1") (pinfunction "GND_1") (pintype "input"))
      (node (ref "IC3") (pin "1") (pinfunction "C_1") (pintype "passive"))
      (node (ref "IC4") (pin "6") (pinfunction "INH_6") (pintype "input"))
      (node (ref "IC4") (pin "7") (pinfunction "VEE_7") (pintype "power_in"))
      (node (ref "IC4") (pin "8") (pinfunction "GND_8") (pintype "power_in"))
      (node (ref "IC5") (pin "1") (pinfunction "GND_1") (pintype "bidirectional"))
      (node (ref "IC5") (pin "21") (pinfunction "BLANK_21") (pintype "bidirectional"))
      (node (ref "IC6") (pin "11") (pinfunction "V-_11") (pintype "power_in"))
      (node (ref "IC6") (pin "12") (pinfunction "+IN_12") (pintype "input"))
      (node (ref "J1") (pin "P1") (pinfunction "1_P1") (pintype "passive"))
      (node (ref "J1") (pin "P2") (pinfunction "2_P2") (pintype "passive"))
      (node (ref "J10") (pin "P1") (pinfunction "1_P1") (pintype "passive"))
      (node (ref "J11") (pin "P1") (pinfunction "1_P1") (pintype "passive"))
      (node (ref "J12") (pin "P1") (pinfunction "1_P1") (pintype "passive"))
      (node (ref "J2") (pin "P1") (pinfunction "1_P1") (pintype "passive"))
      (node (ref "J2") (pin "P2") (pinfunction "2_P2") (pintype "passive"))
      (node (ref "J3") (pin "P1") (pinfunction "1_P1") (pintype "passive"))
      (node (ref "J3") (pin "P2") (pinfunction "2_P2") (pintype "passive"))
      (node (ref "J4") (pin "P1") (pinfunction "1_P1") (pintype "passive"))
      (node (ref "J4") (pin "P2") (pinfunction "2_P2") (pintype "passive"))
      (node (ref "J5") (pin "P1") (pinfunction "1_P1") (pintype "passive"))
      (node (ref "J5") (pin "P2") (pinfunction "2_P2") (pintype "passive"))
      (node (ref "J6") (pin "P1") (pinfunction "1_P1") (pintype "passive"))
      (node (ref "J6") (pin "P2") (pinfunction "2_P2") (pintype "passive"))
      (node (ref "J7") (pin "P1") (pinfunction "1_P1") (pintype "passive"))
      (node (ref "J8") (pin "P1") (pinfunction "1_P1") (pintype "passive"))
      (node (ref "J9") (pin "P1") (pinfunction "1_P1") (pintype "passive"))
      (node (ref "JP1") (pin "3") (pinfunction "3_3") (pintype "passive"))
      (node (ref "JP1") (pin "4") (pinfunction "4_4") (pintype "passive"))
      (node (ref "JP1") (pin "5") (pinfunction "5_5") (pintype "passive"))
      (node (ref "JP1") (pin "6") (pinfunction "6_6") (pintype "passive"))
      (node (ref "JP1") (pin "7") (pinfunction "7_7") (pintype "passive"))
      (node (ref "JP1") (pin "8") (pinfunction "8_8") (pintype "passive"))
      (node (ref "JP2") (pin "1") (pinfunction "1_1") (pintype "passive"))
      (node (ref "POT_A") (pin "P$3") (pinfunction "A_P$3") (pintype "passive"))
      (node (ref "POT_B") (pin "P$3") (pinfunction "A_P$3") (pintype "passive"))
      (node (ref "POT_C") (pin "P$3") (pinfunction "A_P$3") (pintype "passive"))
      (node (ref "Q1") (pin "2") (pinfunction "LID1_2") (pintype "power_in"))
      (node (ref "Q1") (pin "4") (pinfunction "LID2_4") (pintype "power_in"))
      (node (ref "Q2") (pin "E") (pinfunction "E_E") (pintype "passive"))
      (node (ref "Q3") (pin "E") (pinfunction "E_E") (pintype "passive"))
      (node (ref "Q4") (pin "E") (pinfunction "E_E") (pintype "passive"))
      (node (ref "R20") (pin "1") (pinfunction "1_1") (pintype "passive"))
      (node (ref "R21") (pin "1") (pinfunction "1_1") (pintype "passive"))
      (node (ref "R23") (pin "1") (pinfunction "1_1") (pintype "passive"))
      (node (ref "R45") (pin "2") (pinfunction "2_2") (pintype "passive"))
      (node (ref "R46") (pin "2") (pinfunction "2_2") (pintype "passive"))
      (node (ref "R47") (pin "2") (pinfunction "2_2") (pintype "passive"))
      (node (ref "R48") (pin "2") (pinfunction "2_2") (pintype "passive"))
      (node (ref "R49") (pin "2") (pinfunction "2_2") (pintype "passive"))
      (node (ref "R5") (pin "2") (pinfunction "2_2") (pintype "passive"))
      (node (ref "R50") (pin "2") (pinfunction "2_2") (pintype "passive"))
      (node (ref "SLD_A") (pin "1") (pinfunction "A_1") (pintype "passive"))
      (node (ref "SLD_B") (pin "1") (pinfunction "A_1") (pintype "passive"))
      (node (ref "SLD_C") (pin "1") (pinfunction "A_1") (pintype "passive"))
      (node (ref "SW_A") (pin "1") (pinfunction "1_1") (pintype "passive"))
      (node (ref "SW_A") (pin "2") (pinfunction "2_2") (pintype "passive"))
      (node (ref "SW_B") (pin "1") (pinfunction "1_1") (pintype "passive"))
      (node (ref "SW_B") (pin "2") (pinfunction "2_2") (pintype "passive"))
      (node (ref "SW_C") (pin "1") (pinfunction "1_1") (pintype "passive"))
      (node (ref "SW_C") (pin "2") (pinfunction "2_2") (pintype "passive"))
      (node (ref "U$1") (pin "6") (pinfunction "P$6_6") (pintype "bidirectional"))
      (node (ref "U1") (pin "16") (pinfunction "VSS_2_16") (pintype "power_in"))
      (node (ref "U1") (pin "31") (pinfunction "BOOT0_31") (pintype "input"))
      (node (ref "U1") (pin "32") (pinfunction "VSS_1_32") (pintype "power_in"))
      (node (ref "U2") (pin "10") (pinfunction "+IN_10") (pintype "input"))
      (node (ref "U2") (pin "11") (pinfunction "V-_11") (pintype "power_in"))
      (node (ref "U2") (pin "12") (pinfunction "+IN_12") (pintype "input"))
      (node (ref "U2") (pin "3") (pinfunction "+IN_3") (pintype "input"))
      (node (ref "U2") (pin "5") (pinfunction "+IN_5") (pintype "input"))
      (node (ref "U3") (pin "10") (pinfunction "+IN_10") (pintype "input"))
      (node (ref "U3") (pin "12") (pinfunction "+IN_12") (pintype "input"))
      (node (ref "U3") (pin "3") (pinfunction "+IN_3") (pintype "input"))
      (node (ref "U3") (pin "5") (pinfunction "+IN_5") (pintype "input"))
    )
    (net (code "28") (name "LEDS_SCK") (class "Default")
      (node (ref "IC5") (pin "3") (pinfunction "SCLK_3") (pintype "bidirectional"))
      (node (ref "U1") (pin "26") (pinfunction "PB3_26") (pintype "bidirectional"))
    )
    (net (code "29") (name "LEDS_SIN") (class "Default")
      (node (ref "IC5") (pin "2") (pinfunction "SIN_2") (pintype "bidirectional"))
      (node (ref "U1") (pin "28") (pinfunction "PB5_28") (pintype "bidirectional"))
    )
    (net (code "30") (name "LEDS_SS") (class "Default")
      (node (ref "IC5") (pin "4") (pinfunction "LAT_4") (pintype "bidirectional"))
      (node (ref "JP3") (pin "2") (pinfunction "2_2") (pintype "passive"))
    )
    (net (code "31") (name "N_U") (class "Default")
      (node (ref "U2") (pin "6") (pinfunction "-IN_6") (pintype "input"))
      (node (ref "U2") (pin "7") (pinfunction "OUT_7") (pintype "output"))
    )
    (net (code "32") (name "Net-(A-GRN)") (class "Default")
      (node (ref "A") (pin "GREEN_C") (pinfunction "GRN_GREEN_C") (pintype "bidirectional"))
      (node (ref "IC5") (pin "11") (pinfunction "OUT6_11") (pintype "bidirectional"))
    )
    (net (code "33") (name "Net-(A-RED)") (class "Default")
      (node (ref "A") (pin "RED_C") (pinfunction "RED_RED_C") (pintype "bidirectional"))
      (node (ref "IC5") (pin "10") (pinfunction "OUT5_10") (pintype "bidirectional"))
    )
    (net (code "34") (name "Net-(B-GRN)") (class "Default")
      (node (ref "B") (pin "GREEN_C") (pinfunction "GRN_GREEN_C") (pintype "bidirectional"))
      (node (ref "IC5") (pin "9") (pinfunction "OUT4_9") (pintype "bidirectional"))
    )
    (net (code "35") (name "Net-(B-RED)") (class "Default")
      (node (ref "B") (pin "RED_C") (pinfunction "RED_RED_C") (pintype "bidirectional"))
      (node (ref "IC5") (pin "8") (pinfunction "OUT3_8") (pintype "bidirectional"))
    )
    (net (code "36") (name "Net-(C-GRN)") (class "Default")
      (node (ref "C") (pin "GREEN_C") (pinfunction "GRN_GREEN_C") (pintype "bidirectional"))
      (node (ref "IC5") (pin "7") (pinfunction "OUT2_7") (pintype "bidirectional"))
    )
    (net (code "37") (name "Net-(C-RED)") (class "Default")
      (node (ref "C") (pin "RED_C") (pinfunction "RED_RED_C") (pintype "bidirectional"))
      (node (ref "IC5") (pin "6") (pinfunction "OUT1_6") (pintype "bidirectional"))
    )
    (net (code "38") (name "Net-(C1-Pad1)") (class "Default")
      (node (ref "C1") (pin "1") (pinfunction "1_1") (pintype "passive"))
      (node (ref "D1") (pin "C") (pinfunction "C_C") (pintype "passive"))
      (node (ref "L1") (pin "1") (pinfunction "1_1") (pintype "passive"))
      (node (ref "L2") (pin "2") (pinfunction "2_2") (pintype "passive"))
      (node (ref "L3") (pin "2") (pinfunction "2_2") (pintype "passive"))
    )
    (net (code "39") (name "Net-(C3-Pad1)") (class "Default")
      (node (ref "C3") (pin "1") (pinfunction "1_1") (pintype "passive"))
      (node (ref "IC2") (pin "2") (pinfunction "IN_2") (pintype "input"))
      (node (ref "IC2") (pin "4") (pinfunction "IN_4") (pintype "input"))
      (node (ref "L2") (pin "1") (pinfunction "1_1") (pintype "passive"))
    )
    (net (code "40") (name "Net-(C22-Pad2)") (class "Default")
      (node (ref "C22") (pin "2") (pinfunction "2_2") (pintype "passive"))
      (node (ref "Q1") (pin "1") (pinfunction "1_1") (pintype "passive"))
      (node (ref "R6") (pin "2") (pinfunction "2_2") (pintype "passive"))
    )
    (net (code "41") (name "Net-(D2-PadA)") (class "Default")
      (node (ref "D2") (pin "A") (pinfunction "A_A") (pintype "passive"))
      (node (ref "L4") (pin "2") (pinfunction "2_2") (pintype "passive"))
    )
    (net (code "42") (name "Net-(D3-PadC)") (class "Default")
      (node (ref "D3") (pin "C") (pinfunction "C_C") (pintype "passive"))
      (node (ref "Q2") (pin "B") (pinfunction "B_B") (pintype "passive"))
      (node (ref "R18") (pin "2") (pinfunction "2_2") (pintype "passive"))
      (node (ref "R23") (pin "2") (pinfunction "2_2") (pintype "passive"))
    )
    (net (code "43") (name "Net-(D4-PadC)") (class "Default")
      (node (ref "D4") (pin "C") (pinfunction "C_C") (pintype "passive"))
      (node (ref "Q3") (pin "B") (pinfunction "B_B") (pintype "passive"))
      (node (ref "R19") (pin "2") (pinfunction "2_2") (pintype "passive"))
      (node (ref "R20") (pin "2") (pinfunction "2_2") (pintype "passive"))
    )
    (net (code "44") (name "Net-(D5-PadC)") (class "Default")
      (node (ref "D5") (pin "C") (pinfunction "C_C") (pintype "passive"))
      (node (ref "Q4") (pin "B") (pinfunction "B_B") (pintype "passive"))
      (node (ref "R21") (pin "2") (pinfunction "2_2") (pintype "passive"))
      (node (ref "R22") (pin "2") (pinfunction "2_2") (pintype "passive"))
    )
    (net (code "45") (name "Net-(IC1-VI)") (class "Default")
      (node (ref "C5") (pin "1") (pinfunction "1_1") (pintype "passive"))
      (node (ref "IC1") (pin "1") (pinfunction "VI_1") (pintype "input"))
      (node (ref "L1") (pin "2") (pinfunction "2_2") (pintype "passive"))
    )
    (net (code "46") (name "Net-(IC4A-X0)") (class "Default")
      (node (ref "IC4") (pin "13") (pinfunction "X0_13") (pintype "bidirectional"))
      (node (ref "POT_C") (pin "P$2") (pinfunction "S_P$2") (pintype "passive"))
    )
    (net (code "47") (name "Net-(IC4A-X1)") (class "Default")
      (node (ref "IC4") (pin "14") (pinfunction "X1_14") (pintype "bidirectional"))
      (node (ref "SLD_C") (pin "2") (pinfunction "S_2") (pintype "passive"))
    )
    (net (code "48") (name "Net-(IC4A-X2)") (class "Default")
      (node (ref "IC4") (pin "15") (pinfunction "X2_15") (pintype "bidirectional"))
      (node (ref "SLD_B") (pin "2") (pinfunction "S_2") (pintype "passive"))
    )
    (net (code "49") (name "Net-(IC4A-X3)") (class "Default")
      (node (ref "IC4") (pin "12") (pinfunction "X3_12") (pintype "bidirectional"))
      (node (ref "POT_A") (pin "P$2") (pinfunction "S_P$2") (pintype "passive"))
    )
    (net (code "50") (name "Net-(IC4A-X4)") (class "Default")
      (node (ref "IC4") (pin "1") (pinfunction "X4_1") (pintype "bidirectional"))
      (node (ref "SLD_A") (pin "2") (pinfunction "S_2") (pintype "passive"))
    )
    (net (code "51") (name "Net-(IC4A-X5)") (class "Default")
      (node (ref "IC4") (pin "5") (pinfunction "X5_5") (pintype "bidirectional"))
      (node (ref "POT_B") (pin "P$2") (pinfunction "S_P$2") (pintype "passive"))
    )
    (net (code "52") (name "Net-(IC5-IREF)") (class "Default")
      (node (ref "IC5") (pin "23") (pinfunction "IREF_23") (pintype "bidirectional"))
      (node (ref "R5") (pin "1") (pinfunction "1_1") (pintype "passive"))
    )
    (net (code "53") (name "Net-(IC5-OUT7)") (class "Default")
      (node (ref "IC5") (pin "12") (pinfunction "OUT7_12") (pintype "bidirectional"))
      (node (ref "R16") (pin "2") (pinfunction "2_2") (pintype "passive"))
    )
    (net (code "54") (name "Net-(IC5-OUT8)") (class "Default")
      (node (ref "IC5") (pin "13") (pinfunction "OUT8_13") (pintype "bidirectional"))
      (node (ref "R17") (pin "2") (pinfunction "2_2") (pintype "passive"))
    )
    (net (code "55") (name "Net-(IC5-OUT9)") (class "Default")
      (node (ref "IC5") (pin "14") (pinfunction "OUT9_14") (pintype "bidirectional"))
      (node (ref "R15") (pin "2") (pinfunction "2_2") (pintype "passive"))
    )
    (net (code "56") (name "Net-(IC5-VCC)") (class "Default")
      (node (ref "C14") (pin "1") (pinfunction "1_1") (pintype "passive"))
      (node (ref "C15") (pin "1") (pinfunction "1_1") (pintype "passive"))
      (node (ref "IC5") (pin "24") (pinfunction "VCC_24") (pintype "bidirectional"))
      (node (ref "L5") (pin "1") (pinfunction "1_1") (pintype "passive"))
    )
    (net (code "57") (name "Net-(IC6A-+IN)") (class "Default")
      (node (ref "IC6") (pin "3") (pinfunction "+IN_3") (pintype "input"))
      (node (ref "R44") (pin "2") (pinfunction "2_2") (pintype "passive"))
      (node (ref "R47") (pin "1") (pinfunction "1_1") (pintype "passive"))
    )
    (net (code "58") (name "Net-(IC6A--IN)") (class "Default")
      (node (ref "IC6") (pin "2") (pinfunction "-IN_2") (pintype "input"))
      (node (ref "R13") (pin "1") (pinfunction "1_1") (pintype "passive"))
    )
    (net (code "59") (name "Net-(IC6A-OUT)") (class "Default")
      (node (ref "IC6") (pin "1") (pinfunction "OUT_1") (pintype "output"))
      (node (ref "R39") (pin "2") (pinfunction "2_2") (pintype "passive"))
      (node (ref "R44") (pin "1") (pinfunction "1_1") (pintype "passive"))
    )
    (net (code "60") (name "Net-(IC6B-+IN)") (class "Default")
      (node (ref "IC6") (pin "5") (pinfunction "+IN_5") (pintype "input"))
      (node (ref "R41") (pin "2") (pinfunction "2_2") (pintype "passive"))
      (node (ref "R46") (pin "1") (pinfunction "1_1") (pintype "passive"))
    )
    (net (code "61") (name "Net-(IC6B--IN)") (class "Default")
      (node (ref "IC6") (pin "6") (pinfunction "-IN_6") (pintype "input"))
      (node (ref "R12") (pin "1") (pinfunction "1_1") (pintype "passive"))
    )
    (net (code "62") (name "Net-(IC6B-OUT)") (class "Default")
      (node (ref "IC6") (pin "7") (pinfunction "OUT_7") (pintype "output"))
      (node (ref "R38") (pin "2") (pinfunction "2_2") (pintype "passive"))
      (node (ref "R41") (pin "1") (pinfunction "1_1") (pintype "passive"))
    )
    (net (code "63") (name "Net-(IC6C-+IN)") (class "Default")
      (node (ref "IC6") (pin "10") (pinfunction "+IN_10") (pintype "input"))
      (node (ref "R36") (pin "2") (pinfunction "2_2") (pintype "passive"))
      (node (ref "R45") (pin "1") (pinfunction "1_1") (pintype "passive"))
    )
    (net (code "64") (name "Net-(IC6C--IN)") (class "Default")
      (node (ref "IC6") (pin "9") (pinfunction "-IN_9") (pintype "input"))
      (node (ref "R11") (pin "1") (pinfunction "1_1") (pintype "passive"))
    )
    (net (code "65") (name "Net-(IC6C-OUT)") (class "Default")
      (node (ref "IC6") (pin "8") (pinfunction "OUT_8") (pintype "output"))
      (node (ref "R36") (pin "1") (pinfunction "1_1") (pintype "passive"))
      (node (ref "R37") (pin "2") (pinfunction "2_2") (pintype "passive"))
    )
    (net (code "66") (name "Net-(IC6D--IN)") (class "Default")
      (node (ref "IC6") (pin "13") (pinfunction "-IN_13") (pintype "input"))
      (node (ref "IC6") (pin "14") (pinfunction "OUT_14") (pintype "output"))
    )
    (net (code "67") (name "Net-(IC14B-+IN)") (class "Default")
      (node (ref "C32") (pin "2") (pinfunction "2_2") (pintype "passive"))
      (node (ref "IC14") (pin "5") (pinfunction "+IN_5") (pintype "input"))
      (node (ref "R42") (pin "2") (pinfunction "2_2") (pintype "passive"))
      (node (ref "U3") (pin "7") (pinfunction "OUT_7") (pintype "output"))
    )
    (net (code "68") (name "Net-(IC14B--IN)") (class "Default")
      (node (ref "IC14") (pin "6") (pinfunction "-IN_6") (pintype "input"))
      (node (ref "LED_OUT_2") (pin "2") (pinfunction "2_2") (pintype "bidirectional"))
      (node (ref "R49") (pin "1") (pinfunction "1_1") (pintype "passive"))
    )
    (net (code "69") (name "Net-(IC14B-OUT)") (class "Default")
      (node (ref "IC14") (pin "7") (pinfunction "OUT_7") (pintype "output"))
      (node (ref "LED_OUT_2") (pin "1") (pinfunction "1_1") (pintype "bidirectional"))
    )
    (net (code "70") (name "Net-(IC14D-+IN)") (class "Default")
      (node (ref "IC14") (pin "12") (pinfunction "+IN_12") (pintype "input"))
      (node (ref "IC14") (pin "14") (pinfunction "OUT_14") (pintype "output"))
    )
    (net (code "71") (name "Net-(J4-3)") (class "Default")
      (node (ref "J4") (pin "P3") (pinfunction "3_P3") (pintype "passive"))
      (node (ref "R24") (pin "2") (pinfunction "2_2") (pintype "passive"))
    )
    (net (code "72") (name "Net-(J6-3)") (class "Default")
      (node (ref "J6") (pin "P3") (pinfunction "3_P3") (pintype "passive"))
      (node (ref "R26") (pin "2") (pinfunction "2_2") (pintype "passive"))
    )
    (net (code "73") (name "Net-(J10-3)") (class "Default")
      (node (ref "J10") (pin "P3") (pinfunction "3_P3") (pintype "passive"))
      (node (ref "R35") (pin "1") (pinfunction "1_1") (pintype "passive"))
      (node (ref "R40") (pin "1") (pinfunction "1_1") (pintype "passive"))
    )
    (net (code "74") (name "Net-(J11-3)") (class "Default")
      (node (ref "J11") (pin "P3") (pinfunction "3_P3") (pintype "passive"))
      (node (ref "R29") (pin "1") (pinfunction "1_1") (pintype "passive"))
      (node (ref "R42") (pin "1") (pinfunction "1_1") (pintype "passive"))
    )
    (net (code "75") (name "Net-(J12-3)") (class "Default")
      (node (ref "J12") (pin "P3") (pinfunction "3_P3") (pintype "passive"))
      (node (ref "R32") (pin "1") (pinfunction "1_1") (pintype "passive"))
      (node (ref "R43") (pin "1") (pinfunction "1_1") (pintype "passive"))
    )
    (net (code "76") (name "Net-(LED_OUT_1-Pad2)") (class "Default")
      (node (ref "LED_OUT_1") (pin "2") (pinfunction "2_2") (pintype "bidirectional"))
      (node (ref "R48") (pin "1") (pinfunction "1_1") (pintype "passive"))
    )
    (net (code "77") (name "Net-(LED_OUT_3-Pad2)") (class "Default")
      (node (ref "LED_OUT_3") (pin "2") (pinfunction "2_2") (pintype "bidirectional"))
      (node (ref "R50") (pin "1") (pinfunction "1_1") (pintype "passive"))
    )
    (net (code "78") (name "Net-(Q1B-2)") (class "Default")
      (node (ref "C21") (pin "2") (pinfunction "2_2") (pintype "passive"))
      (node (ref "Q1") (pin "3") (pinfunction "2_3") (pintype "passive"))
      (node (ref "R9") (pin "2") (pinfunction "2_2") (pintype "passive"))
    )
    (net (code "79") (name "Net-(SLD_AA-C)") (class "Default")
      (node (ref "R16") (pin "1") (pinfunction "1_1") (pintype "passive"))
      (node (ref "SLD_A") (pin "E") (pinfunction "C_E") (pintype "passive"))
    )
    (net (code "80") (name "Net-(SLD_BA-C)") (class "Default")
      (node (ref "R17") (pin "1") (pinfunction "1_1") (pintype "passive"))
      (node (ref "SLD_B") (pin "E") (pinfunction "C_E") (pintype "passive"))
    )
    (net (code "81") (name "Net-(SLD_CA-C)") (class "Default")
      (node (ref "R15") (pin "1") (pinfunction "1_1") (pintype "passive"))
      (node (ref "SLD_C") (pin "E") (pinfunction "C_E") (pintype "passive"))
    )
    (net (code "82") (name "Net-(U1-PF0{slash}OSC_IN)") (class "Default")
      (node (ref "R9") (pin "1") (pinfunction "1_1") (pintype "passive"))
      (node (ref "U1") (pin "2") (pinfunction "PF0/OSC_IN_2") (pintype "bidirectional"))
    )
    (net (code "83") (name "Net-(U1-PF1{slash}OSC_OUT)") (class "Default")
      (node (ref "R6") (pin "1") (pinfunction "1_1") (pintype "passive"))
      (node (ref "U1") (pin "3") (pinfunction "PF1/OSC_OUT_3") (pintype "bidirectional"))
    )
    (net (code "84") (name "Net-(U2A--IN)") (class "Default")
      (node (ref "C30") (pin "1") (pinfunction "1_1") (pintype "passive"))
      (node (ref "R14") (pin "2") (pinfunction "2_2") (pintype "passive"))
      (node (ref "R2") (pin "1") (pinfunction "1_1") (pintype "passive"))
      (node (ref "R26") (pin "1") (pinfunction "1_1") (pintype "passive"))
      (node (ref "U2") (pin "2") (pinfunction "-IN_2") (pintype "input"))
    )
    (net (code "85") (name "Net-(U2C--IN)") (class "Default")
      (node (ref "C23") (pin "1") (pinfunction "1_1") (pintype "passive"))
      (node (ref "R25") (pin "1") (pinfunction "1_1") (pintype "passive"))
      (node (ref "R3") (pin "1") (pinfunction "1_1") (pintype "passive"))
      (node (ref "R7") (pin "2") (pinfunction "2_2") (pintype "passive"))
      (node (ref "U2") (pin "9") (pinfunction "-IN_9") (pintype "input"))
    )
    (net (code "86") (name "Net-(U2D--IN)") (class "Default")
      (node (ref "C24") (pin "1") (pinfunction "1_1") (pintype "passive"))
      (node (ref "R24") (pin "1") (pinfunction "1_1") (pintype "passive"))
      (node (ref "R4") (pin "1") (pinfunction "1_1") (pintype "passive"))
      (node (ref "R8") (pin "2") (pinfunction "2_2") (pintype "passive"))
      (node (ref "U2") (pin "13") (pinfunction "-IN_13") (pintype "input"))
    )
    (net (code "87") (name "Net-(U3A--IN)") (class "Default")
      (node (ref "C33") (pin "1") (pinfunction "1_1") (pintype "passive"))
      (node (ref "R30") (pin "1") (pinfunction "1_1") (pintype "passive"))
      (node (ref "R31") (pin "1") (pinfunction "1_1") (pintype "passive"))
      (node (ref "R32") (pin "2") (pinfunction "2_2") (pintype "passive"))
      (node (ref "U3") (pin "2") (pinfunction "-IN_2") (pintype "input"))
    )
    (net (code "88") (name "Net-(U3A-OUT)") (class "Default")
      (node (ref "C33") (pin "2") (pinfunction "2_2") (pintype "passive"))
      (node (ref "R43") (pin "2") (pinfunction "2_2") (pintype "passive"))
      (node (ref "U3") (pin "1") (pinfunction "OUT_1") (pintype "output"))
    )
    (net (code "89") (name "Net-(U3B--IN)") (class "Default")
      (node (ref "C32") (pin "1") (pinfunction "1_1") (pintype "passive"))
      (node (ref "R27") (pin "1") (pinfunction "1_1") (pintype "passive"))
      (node (ref "R28") (pin "1") (pinfunction "1_1") (pintype "passive"))
      (node (ref "R29") (pin "2") (pinfunction "2_2") (pintype "passive"))
      (node (ref "U3") (pin "6") (pinfunction "-IN_6") (pintype "input"))
    )
    (net (code "90") (name "Net-(U3C--IN)") (class "Default")
      (node (ref "C34") (pin "1") (pinfunction "1_1") (pintype "passive"))
      (node (ref "R33") (pin "1") (pinfunction "1_1") (pintype "passive"))
      (node (ref "R34") (pin "1") (pinfunction "1_1") (pintype "passive"))
      (node (ref "R35") (pin "2") (pinfunction "2_2") (pintype "passive"))
      (node (ref "U3") (pin "9") (pinfunction "-IN_9") (pintype "input"))
    )
    (net (code "91") (name "Net-(U3C-OUT)") (class "Default")
      (node (ref "C34") (pin "2") (pinfunction "2_2") (pintype "passive"))
      (node (ref "R40") (pin "2") (pinfunction "2_2") (pintype "passive"))
      (node (ref "U3") (pin "8") (pinfunction "OUT_8") (pintype "output"))
    )
    (net (code "92") (name "Net-(U3D--IN)") (class "Default")
      (node (ref "U3") (pin "13") (pinfunction "-IN_13") (pintype "input"))
      (node (ref "U3") (pin "14") (pinfunction "OUT_14") (pintype "output"))
    )
    (net (code "93") (name "POTS_ADDR_A") (class "Default")
      (node (ref "IC4") (pin "11") (pinfunction "A_11") (pintype "input"))
      (node (ref "U1") (pin "13") (pinfunction "PA7_13") (pintype "bidirectional"))
    )
    (net (code "94") (name "POTS_ADDR_B") (class "Default")
      (node (ref "IC4") (pin "10") (pinfunction "B_10") (pintype "input"))
      (node (ref "U1") (pin "18") (pinfunction "PA8_18") (pintype "bidirectional"))
    )
    (net (code "95") (name "POTS_ADDR_C") (class "Default")
      (node (ref "IC4") (pin "9") (pinfunction "C_9") (pintype "input"))
      (node (ref "U1") (pin "19") (pinfunction "PA9_19") (pintype "bidirectional"))
    )
    (net (code "96") (name "RESET") (class "Default")
      (node (ref "C28") (pin "1") (pinfunction "1_1") (pintype "passive"))
      (node (ref "JP2") (pin "4") (pinfunction "4_4") (pintype "passive"))
      (node (ref "R10") (pin "2") (pinfunction "2_2") (pintype "passive"))
      (node (ref "U1") (pin "4") (pinfunction "NRST_4") (pintype "bidirectional"))
    )
    (net (code "97") (name "SWCLK") (class "Default")
      (node (ref "JP2") (pin "3") (pinfunction "3_3") (pintype "passive"))
      (node (ref "U1") (pin "24") (pinfunction "PA14_24") (pintype "bidirectional"))
    )
    (net (code "98") (name "SWDIO_SS") (class "Default")
      (node (ref "JP2") (pin "2") (pinfunction "2_2") (pintype "passive"))
      (node (ref "JP3") (pin "1") (pinfunction "1_1") (pintype "passive"))
      (node (ref "U1") (pin "23") (pinfunction "PA13_23") (pintype "bidirectional"))
    )
    (net (code "99") (name "SW_MODE_A") (class "Default")
      (node (ref "SW_A") (pin "3") (pinfunction "3_3") (pintype "passive"))
      (node (ref "SW_A") (pin "4") (pinfunction "4_4") (pintype "passive"))
      (node (ref "U1") (pin "27") (pinfunction "PB4_27") (pintype "bidirectional"))
    )
    (net (code "100") (name "SW_MODE_B") (class "Default")
      (node (ref "SW_B") (pin "3") (pinfunction "3_3") (pintype "passive"))
      (node (ref "SW_B") (pin "4") (pinfunction "4_4") (pintype "passive"))
      (node (ref "U1") (pin "29") (pinfunction "PB6_29") (pintype "bidirectional"))
    )
    (net (code "101") (name "SW_MODE_C") (class "Default")
      (node (ref "SW_C") (pin "3") (pinfunction "3_3") (pintype "passive"))
      (node (ref "SW_C") (pin "4") (pinfunction "4_4") (pintype "passive"))
      (node (ref "U1") (pin "30") (pinfunction "PB7_30") (pintype "bidirectional"))
    )
    (net (code "102") (name "VCC") (class "Default")
      (node (ref "C2") (pin "1") (pinfunction "1_1") (pintype "passive"))
      (node (ref "C31") (pin "1") (pinfunction "1_1") (pintype "passive"))
      (node (ref "C35") (pin "1") (pinfunction "1_1") (pintype "passive"))
      (node (ref "C36") (pin "1") (pinfunction "1_1") (pintype "passive"))
      (node (ref "C4") (pin "1") (pinfunction "1_1") (pintype "passive"))
      (node (ref "IC14") (pin "4") (pinfunction "V+_4") (pintype "power_in"))
      (node (ref "IC6") (pin "4") (pinfunction "V+_4") (pintype "power_in"))
      (node (ref "L3") (pin "1") (pinfunction "1_1") (pintype "passive"))
      (node (ref "U$1") (pin "1") (pinfunction "P$1_1") (pintype "bidirectional"))
      (node (ref "U3") (pin "4") (pinfunction "V+_4") (pintype "power_in"))
    )
    (net (code "103") (name "VEE") (class "Default")
      (node (ref "C10") (pin "2") (pinfunction "2_2") (pintype "passive"))
      (node (ref "C25") (pin "2") (pinfunction "2_2") (pintype "passive"))
      (node (ref "C37") (pin "2") (pinfunction "2_2") (pintype "passive"))
      (node (ref "C9") (pin "2") (pinfunction "2_2") (pintype "passive"))
      (node (ref "IC14") (pin "11") (pinfunction "V-_11") (pintype "power_in"))
      (node (ref "L4") (pin "1") (pinfunction "1_1") (pintype "passive"))
      (node (ref "R1") (pin "1") (pinfunction "1_1") (pintype "passive"))
      (node (ref "U$1") (pin "2") (pinfunction "P$2_2") (pintype "bidirectional"))
      (node (ref "U3") (pin "11") (pinfunction "V-_11") (pintype "power_in"))
    )
    (net (code "104") (name "unconnected-(IC4A-X7-Pad4)") (class "Default")
      (node (ref "IC4") (pin "4") (pinfunction "X7_4") (pintype "bidirectional"))
    )
    (net (code "105") (name "unconnected-(IC5-OUT0-Pad5)") (class "Default")
      (node (ref "IC5") (pin "5") (pinfunction "OUT0_5") (pintype "bidirectional"))
    )
    (net (code "106") (name "unconnected-(IC5-OUT10-Pad15)") (class "Default")
      (node (ref "IC5") (pin "15") (pinfunction "OUT10_15") (pintype "bidirectional"))
    )
    (net (code "107") (name "unconnected-(IC5-OUT11-Pad16)") (class "Default")
      (node (ref "IC5") (pin "16") (pinfunction "OUT11_16") (pintype "bidirectional"))
    )
    (net (code "108") (name "unconnected-(IC5-OUT12-Pad17)") (class "Default")
      (node (ref "IC5") (pin "17") (pinfunction "OUT12_17") (pintype "bidirectional"))
    )
    (net (code "109") (name "unconnected-(IC5-OUT13-Pad18)") (class "Default")
      (node (ref "IC5") (pin "18") (pinfunction "OUT13_18") (pintype "bidirectional"))
    )
    (net (code "110") (name "unconnected-(IC5-OUT14-Pad19)") (class "Default")
      (node (ref "IC5") (pin "19") (pinfunction "OUT14_19") (pintype "bidirectional"))
    )
    (net (code "111") (name "unconnected-(IC5-OUT15-Pad20)") (class "Default")
      (node (ref "IC5") (pin "20") (pinfunction "OUT15_20") (pintype "bidirectional"))
    )
    (net (code "112") (name "unconnected-(IC5-SOUT-Pad22)") (class "Default")
      (node (ref "IC5") (pin "22") (pinfunction "SOUT_22") (pintype "bidirectional"))
    )
    (net (code "113") (name "unconnected-(IC14A-+IN-Pad3)") (class "Default")
      (node (ref "IC14") (pin "3") (pinfunction "+IN_3") (pintype "input"))
    )
    (net (code "114") (name "unconnected-(IC14A--IN-Pad2)") (class "Default")
      (node (ref "IC14") (pin "2") (pinfunction "-IN_2") (pintype "input"))
    )
    (net (code "115") (name "unconnected-(IC14A-OUT-Pad1)") (class "Default")
      (node (ref "IC14") (pin "1") (pinfunction "OUT_1") (pintype "output"))
    )
    (net (code "116") (name "unconnected-(IC14C-+IN-Pad10)") (class "Default")
      (node (ref "IC14") (pin "10") (pinfunction "+IN_10") (pintype "input"))
    )
    (net (code "117") (name "unconnected-(IC14C--IN-Pad9)") (class "Default")
      (node (ref "IC14") (pin "9") (pinfunction "-IN_9") (pintype "input"))
    )
    (net (code "118") (name "unconnected-(IC14C-OUT-Pad8)") (class "Default")
      (node (ref "IC14") (pin "8") (pinfunction "OUT_8") (pintype "output"))
    )
    (net (code "119") (name "unconnected-(J7-2-PadP2)") (class "Default")
      (node (ref "J7") (pin "P2") (pinfunction "2_P2") (pintype "passive"))
    )
    (net (code "120") (name "unconnected-(J8-2-PadP2)") (class "Default")
      (node (ref "J8") (pin "P2") (pinfunction "2_P2") (pintype "passive"))
    )
    (net (code "121") (name "unconnected-(J9-2-PadP2)") (class "Default")
      (node (ref "J9") (pin "P2") (pinfunction "2_P2") (pintype "passive"))
    )
    (net (code "122") (name "unconnected-(J10-2-PadP2)") (class "Default")
      (node (ref "J10") (pin "P2") (pinfunction "2_P2") (pintype "passive"))
    )
    (net (code "123") (name "unconnected-(J11-2-PadP2)") (class "Default")
      (node (ref "J11") (pin "P2") (pinfunction "2_P2") (pintype "passive"))
    )
    (net (code "124") (name "unconnected-(J12-2-PadP2)") (class "Default")
      (node (ref "J12") (pin "P2") (pinfunction "2_P2") (pintype "passive"))
    )
    (net (code "125") (name "unconnected-(LED_OUT_1-Pad1)") (class "Default")
      (node (ref "LED_OUT_1") (pin "1") (pinfunction "1_1") (pintype "bidirectional"))
    )
    (net (code "126") (name "unconnected-(LED_OUT_3-Pad1)") (class "Default")
      (node (ref "LED_OUT_3") (pin "1") (pinfunction "1_1") (pintype "bidirectional"))
    )
  )
)
